# 03-Main.net
KiCad netlist of a schematic drawn in Altium Designer
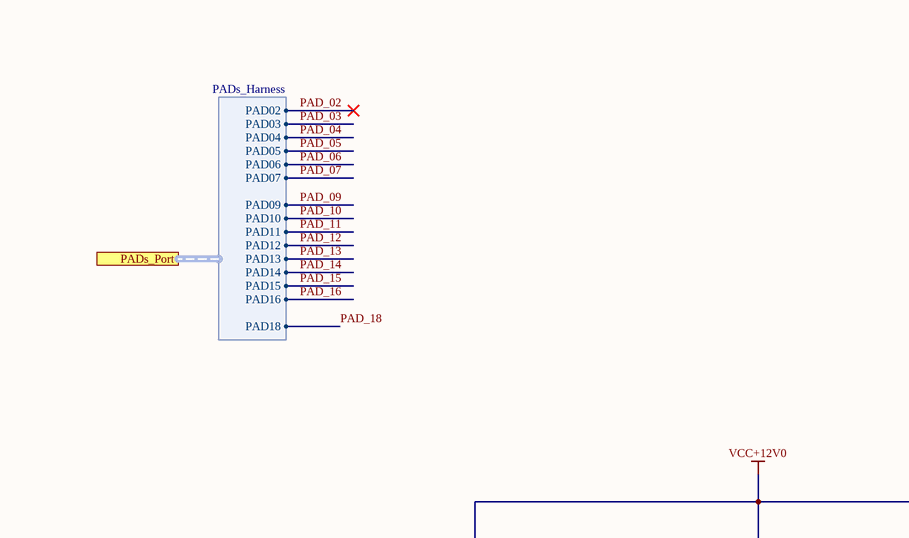
[diagram p0: 03-Main.SchDoc, top left]
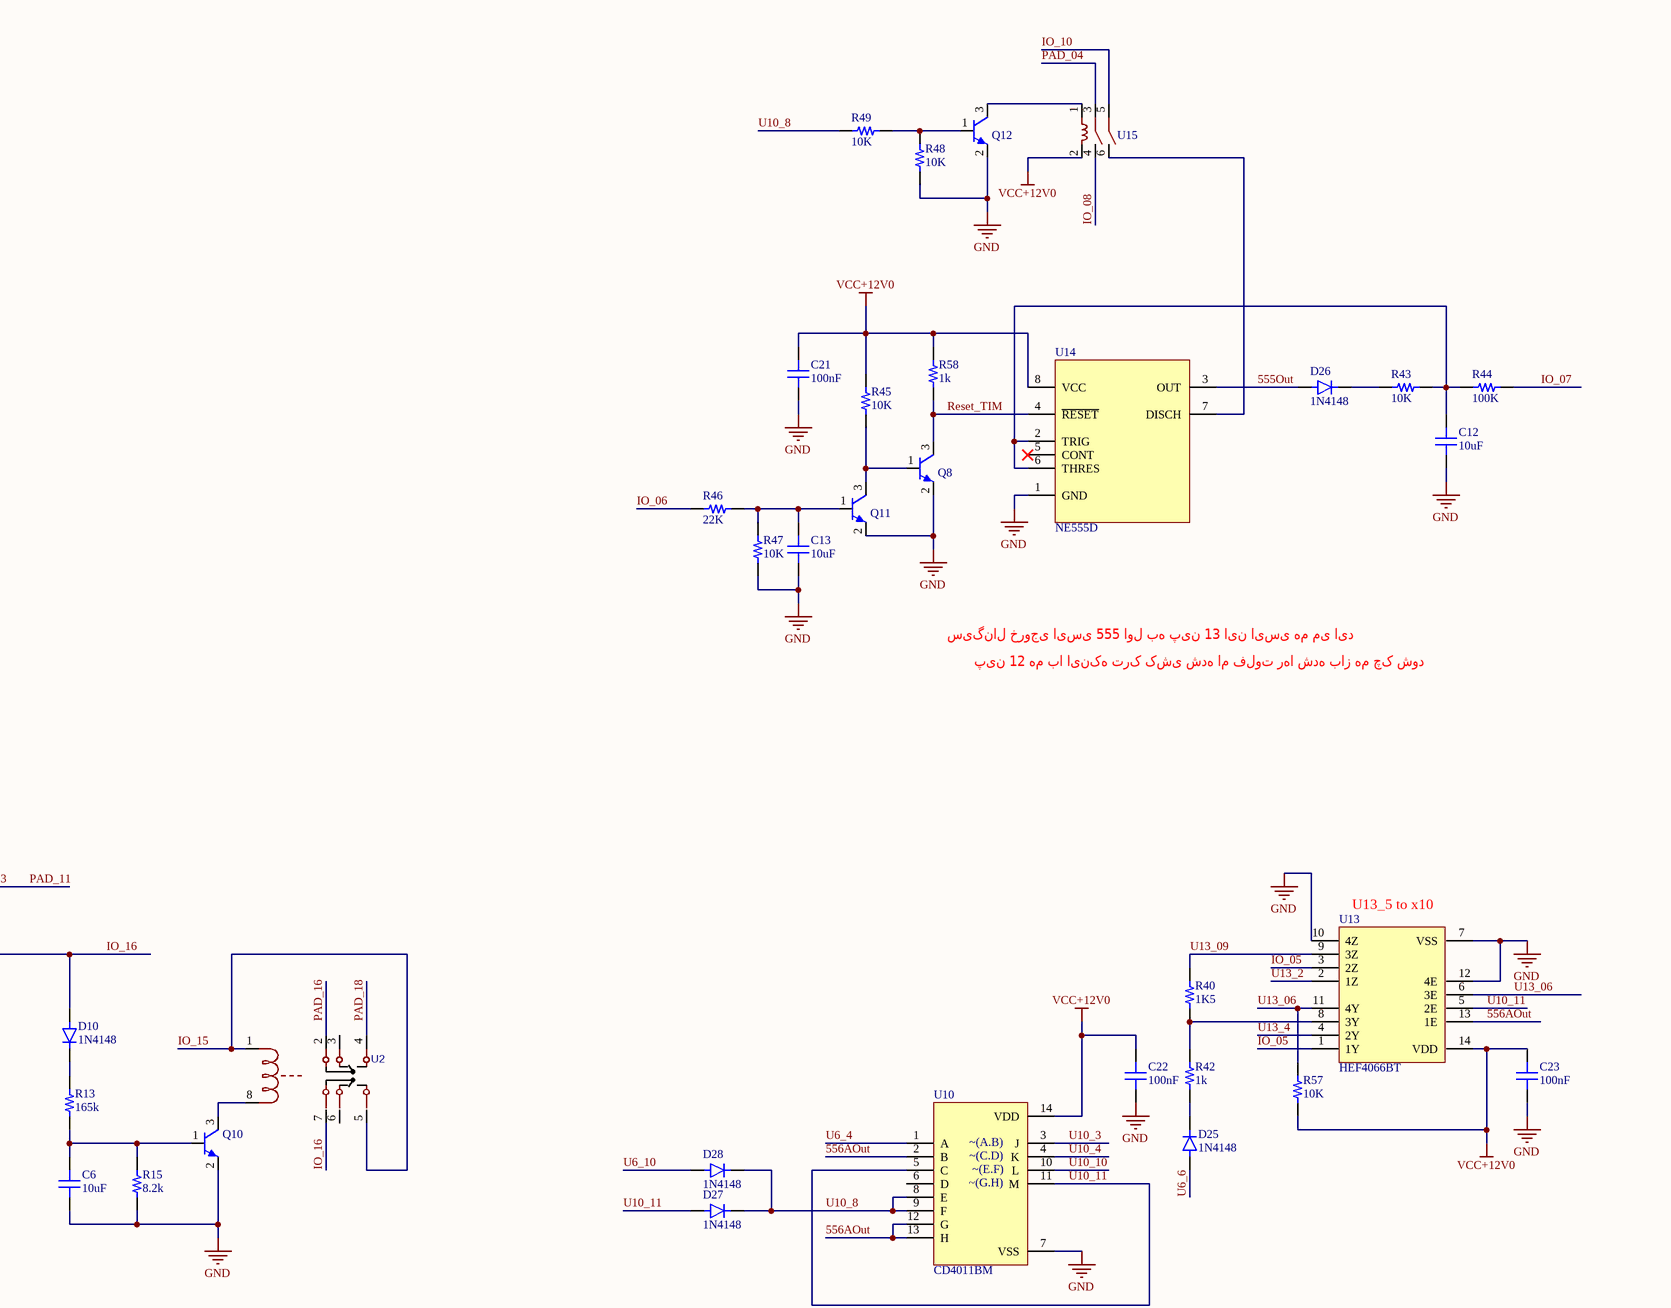
[diagram p1: 03-Main.SchDoc, top right]
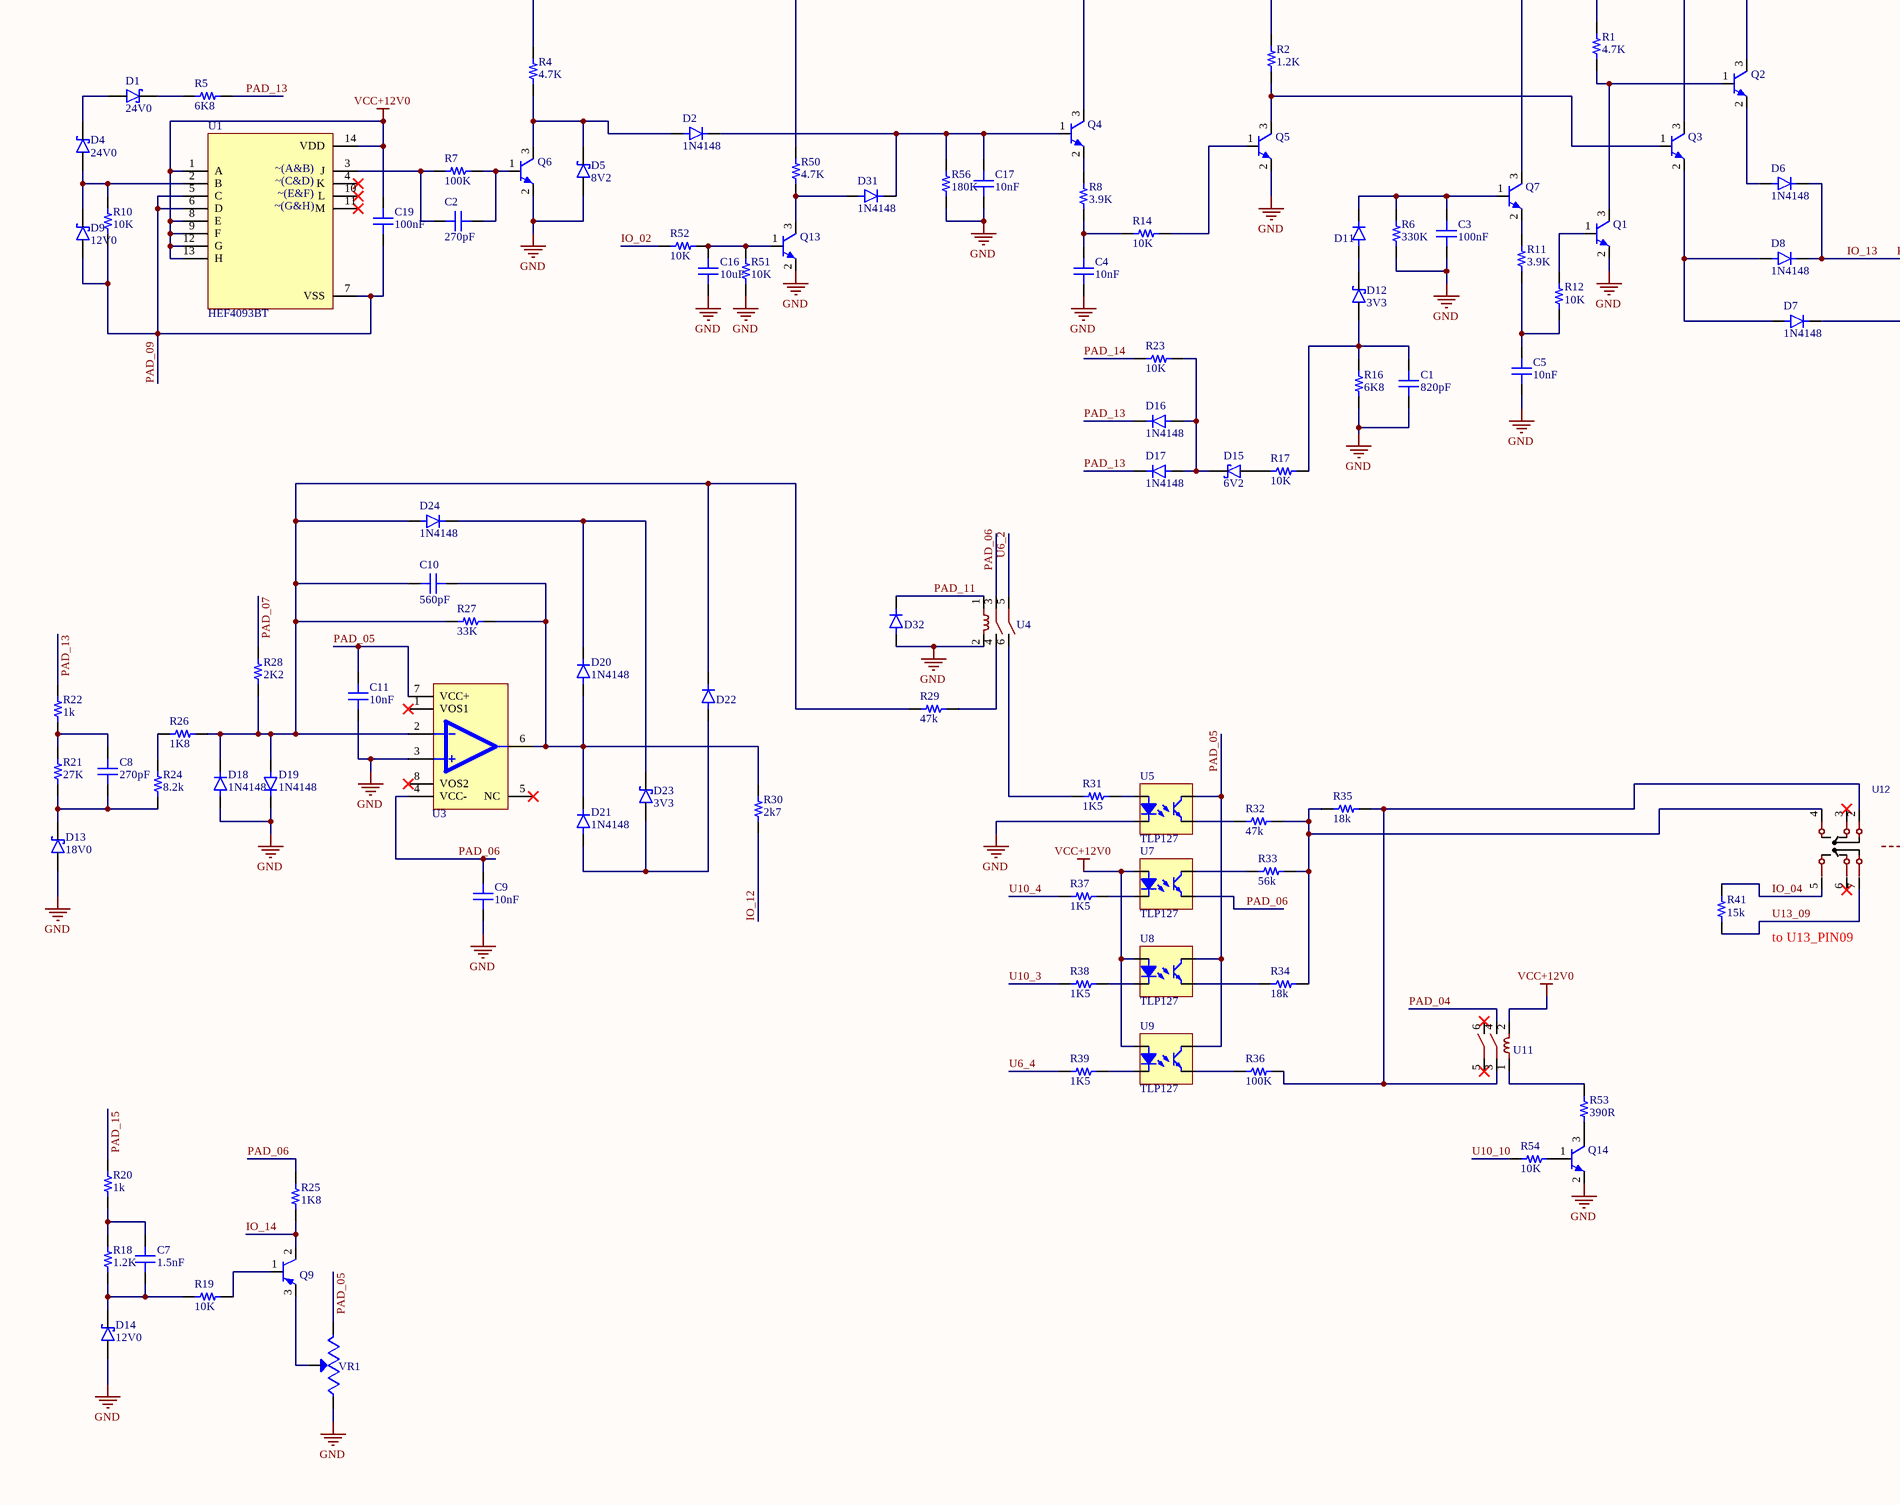
[diagram p2: 03-Main.SchDoc, bottom left]
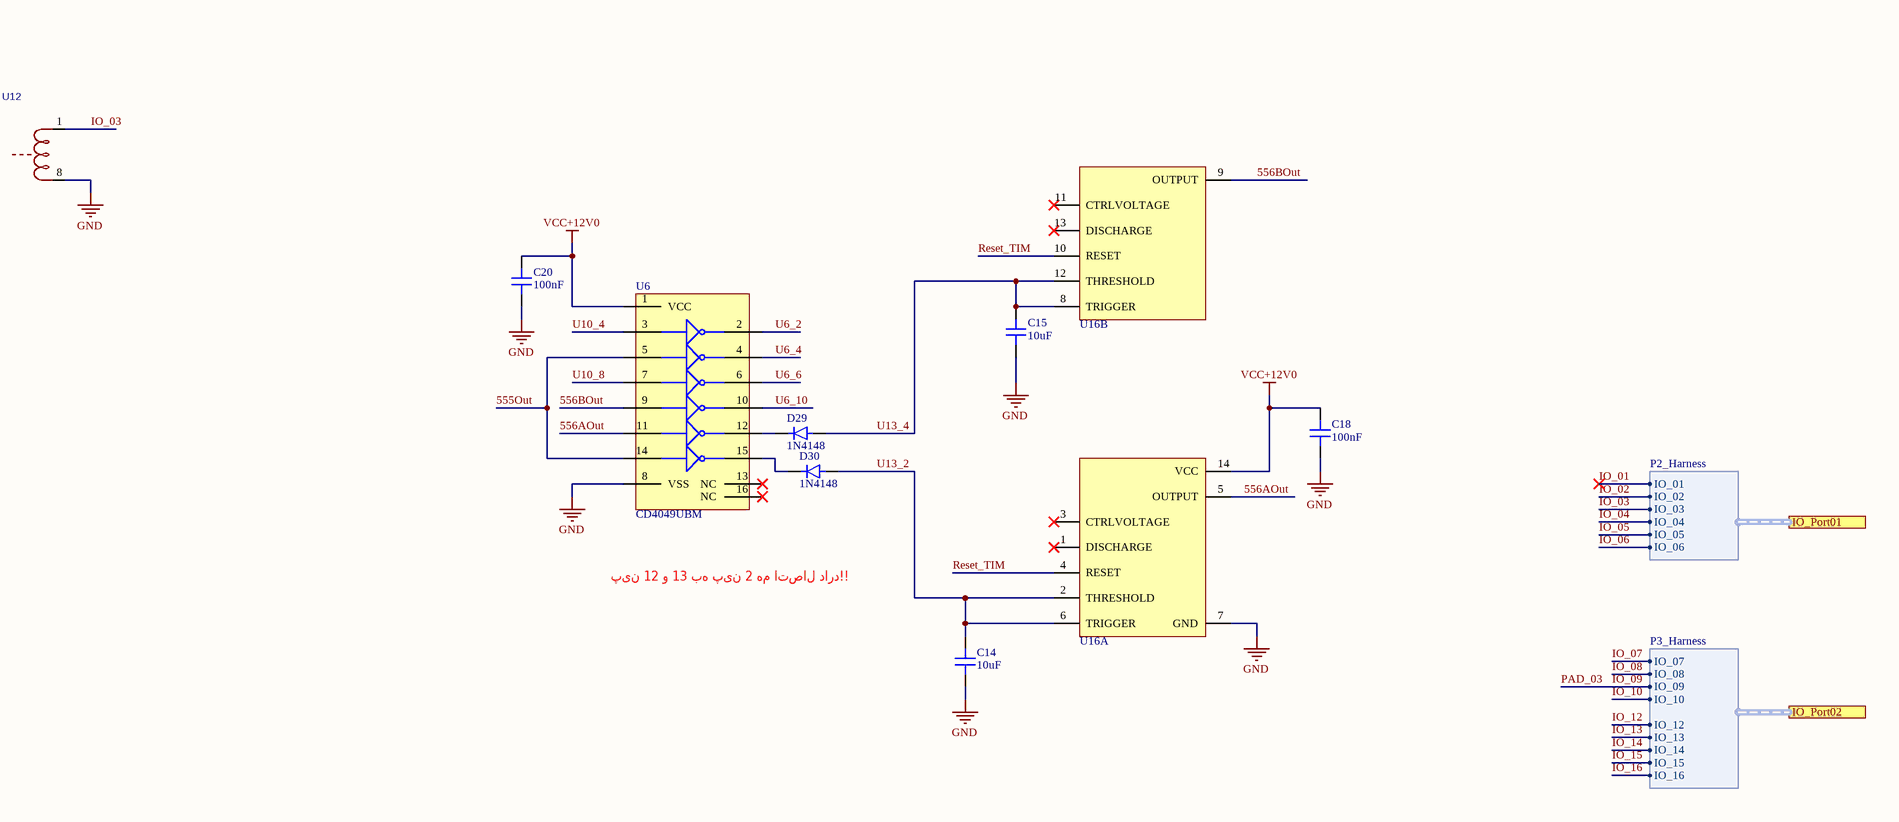
[diagram p3: 03-Main.SchDoc, bottom right]

(export (version "E")
  (design (tool "Eeschema 10.0.6"))
  (components
    (comp (ref "C1")
      (value "820pF")
      (footprint "Cap0805")
      (description "Cap 0805 820pF")
      (fields (field (name "PART NUMBER") "Cap-0805-820pF"))
      (libsource (lib "My Library") (part "Unpolarised Capacitor"))
    )
    (comp (ref "C2")
      (value "270pF")
      (footprint "Cap0805")
      (description "Cap 0805 270pF")
      (fields (field (name "PART NUMBER") "Cap-0805-270pF"))
      (libsource (lib "My Library") (part "Unpolarised Capacitor"))
    )
    (comp (ref "C3")
      (value "100nF")
      (footprint "Cap0805")
      (description "Cap 0805 100nF")
      (fields (field (name "PART NUMBER") "Cap-0805-100nF") (field (name "MANUFACTURER") "---"))
      (libsource (lib "My Library") (part "Unpolarised Capacitor"))
    )
    (comp (ref "C4")
      (value "10nF")
      (footprint "Cap0805")
      (description "Cap 0805 10nF")
      (fields (field (name "PART NUMBER") "Cap-0805-10nF"))
      (libsource (lib "My Library") (part "Unpolarised Capacitor"))
    )
    (comp (ref "C5")
      (value "10nF")
      (footprint "Cap0805")
      (description "Cap 0805 10nF")
      (fields (field (name "PART NUMBER") "Cap-0805-10nF"))
      (libsource (lib "My Library") (part "Unpolarised Capacitor"))
    )
    (comp (ref "C6")
      (value "10uF")
      (footprint "Cap0603")
      (description "Cap 0603 10uF")
      (fields (field (name "PART NUMBER") "Cap-0603-10uF") (field (name "MANUFACTURER") "---"))
      (libsource (lib "My Library") (part "Unpolarised Capacitor"))
    )
    (comp (ref "C7")
      (value "1.5nF")
      (footprint "Cap0805")
      (description "Cap 0805 1.5nF")
      (fields (field (name "PART NUMBER") "Cap-0805-1.5nF"))
      (libsource (lib "My Library") (part "Unpolarised Capacitor"))
    )
    (comp (ref "C8")
      (value "270pF")
      (footprint "Cap0805")
      (description "Cap 0805 270pF")
      (fields (field (name "PART NUMBER") "Cap-0805-270pF"))
      (libsource (lib "My Library") (part "Unpolarised Capacitor"))
    )
    (comp (ref "C9")
      (value "10nF")
      (footprint "Cap0805")
      (description "Cap 0805 10nF")
      (fields (field (name "PART NUMBER") "Cap-0805-10nF"))
      (libsource (lib "My Library") (part "Unpolarised Capacitor"))
    )
    (comp (ref "C10")
      (value "560pF")
      (footprint "Cap0603")
      (description "Cap 0603 560pF")
      (fields (field (name "PART NUMBER") "Cap-0603-560pF"))
      (libsource (lib "My Library") (part "Unpolarised Capacitor"))
    )
    (comp (ref "C11")
      (value "10nF")
      (footprint "Cap0805")
      (description "Cap 0805 10nF")
      (fields (field (name "PART NUMBER") "Cap-0805-10nF"))
      (libsource (lib "My Library") (part "Unpolarised Capacitor"))
    )
    (comp (ref "C12")
      (value "10uF")
      (footprint "Cap1206")
      (description "Cap 1206 10uF 50V")
      (fields (field (name "PART NUMBER") "Cap-1206-10uF") (field (name "MANUFACTURER") "---"))
      (libsource (lib "My Library") (part "Unpolarised Capacitor"))
    )
    (comp (ref "C13")
      (value "10uF")
      (footprint "Cap0805")
      (description "Cap 0805 10uF")
      (fields (field (name "PART NUMBER") "Cap-0805-10uF") (field (name "MANUFACTURER") "---"))
      (libsource (lib "My Library") (part "Unpolarised Capacitor"))
    )
    (comp (ref "C14")
      (value "10uF")
      (footprint "Cap1206")
      (description "Cap 1206 10uF 50V")
      (fields (field (name "PART NUMBER") "Cap-1206-10uF") (field (name "MANUFACTURER") "---"))
      (libsource (lib "My Library") (part "Unpolarised Capacitor"))
    )
    (comp (ref "C15")
      (value "10uF")
      (footprint "Cap1206")
      (description "Cap 1206 10uF 50V")
      (fields (field (name "PART NUMBER") "Cap-1206-10uF") (field (name "MANUFACTURER") "---"))
      (libsource (lib "My Library") (part "Unpolarised Capacitor"))
    )
    (comp (ref "C16")
      (value "10uF")
      (footprint "Cap1206")
      (description "Cap 1206 10uF 50V")
      (fields (field (name "PART NUMBER") "Cap-1206-10uF") (field (name "MANUFACTURER") "---"))
      (libsource (lib "My Library") (part "Unpolarised Capacitor"))
    )
    (comp (ref "C17")
      (value "10nF")
      (footprint "Cap0805")
      (description "Cap 0805 10nF")
      (fields (field (name "PART NUMBER") "Cap-0805-10nF"))
      (libsource (lib "My Library") (part "Unpolarised Capacitor"))
    )
    (comp (ref "C18")
      (value "100nF")
      (footprint "Cap0805")
      (description "Cap 0805 100nF")
      (fields (field (name "PART NUMBER") "Cap-0805-100nF") (field (name "MANUFACTURER") "---"))
      (libsource (lib "My Library") (part "Unpolarised Capacitor"))
    )
    (comp (ref "C19")
      (value "100nF")
      (footprint "Cap0805")
      (description "Cap 0805 100nF")
      (fields (field (name "PART NUMBER") "Cap-0805-100nF") (field (name "MANUFACTURER") "---"))
      (libsource (lib "My Library") (part "Unpolarised Capacitor"))
    )
    (comp (ref "C20")
      (value "100nF")
      (footprint "Cap0805")
      (description "Cap 0805 100nF")
      (fields (field (name "PART NUMBER") "Cap-0805-100nF") (field (name "MANUFACTURER") "---"))
      (libsource (lib "My Library") (part "Unpolarised Capacitor"))
    )
    (comp (ref "C21")
      (value "100nF")
      (footprint "Cap0805")
      (description "Cap 0805 100nF")
      (fields (field (name "PART NUMBER") "Cap-0805-100nF") (field (name "MANUFACTURER") "---"))
      (libsource (lib "My Library") (part "Unpolarised Capacitor"))
    )
    (comp (ref "C22")
      (value "100nF")
      (footprint "Cap0805")
      (description "Cap 0805 100nF")
      (fields (field (name "PART NUMBER") "Cap-0805-100nF") (field (name "MANUFACTURER") "---"))
      (libsource (lib "My Library") (part "Unpolarised Capacitor"))
    )
    (comp (ref "C23")
      (value "100nF")
      (footprint "Cap0805")
      (description "Cap 0805 100nF")
      (fields (field (name "PART NUMBER") "Cap-0805-100nF") (field (name "MANUFACTURER") "---"))
      (libsource (lib "My Library") (part "Unpolarised Capacitor"))
    )
    (comp (ref "D1")
      (value "24V0")
      (footprint "Melf")
      (description "Zener Diode Melf")
      (fields (field (name "MP") "TMMBAT41") (field (name "MF") "STMicroelectronics"))
      (libsource (lib "My Library") (part "Zener"))
    )
    (comp (ref "D2")
      (value "1N4148")
      (footprint "SOD-123")
      (description "Diode Standard 75 V 300mA (DC) Through Hole DO-35 Mimi Melf")
      (fields (field (name "MF") "ON Semiconductor"))
      (libsource (lib "My Library") (part "Diode"))
    )
    (comp (ref "D4")
      (value "24V0")
      (footprint "Melf")
      (description "Zener Diode Melf")
      (fields (field (name "MF") "STMicroelectronics") (field (name "MP") "TMMBAT41"))
      (libsource (lib "My Library") (part "Zener"))
    )
    (comp (ref "D5")
      (value "8V2")
      (footprint "Melf")
      (description "Zener Diode Melf")
      (fields (field (name "MP") "TMMBAT41") (field (name "MF") "STMicroelectronics"))
      (libsource (lib "My Library") (part "Zener"))
    )
    (comp (ref "D6")
      (value "1N4148")
      (footprint "SOD-123")
      (description "Diode Standard 75 V 300mA (DC) Through Hole DO-35 Mimi Melf")
      (fields (field (name "MF") "ON Semiconductor"))
      (libsource (lib "My Library") (part "Diode"))
    )
    (comp (ref "D7")
      (value "1N4148")
      (footprint "SOD-123")
      (description "Diode Standard 75 V 300mA (DC) Through Hole DO-35 Mimi Melf")
      (fields (field (name "MF") "ON Semiconductor"))
      (libsource (lib "My Library") (part "Diode"))
    )
    (comp (ref "D8")
      (value "1N4148")
      (footprint "SOD-123")
      (description "Diode Standard 75 V 300mA (DC) Through Hole DO-35 Mimi Melf")
      (fields (field (name "MF") "ON Semiconductor"))
      (libsource (lib "My Library") (part "Diode"))
    )
    (comp (ref "D9")
      (value "12V0")
      (footprint "Melf")
      (description "Zener Diode Melf")
      (fields (field (name "MP") "TMMBAT41") (field (name "MF") "STMicroelectronics"))
      (libsource (lib "My Library") (part "Zener"))
    )
    (comp (ref "D10")
      (value "1N4148")
      (footprint "SOD-123")
      (description "Diode Standard 75 V 300mA (DC) Through Hole DO-35 Mimi Melf")
      (fields (field (name "MF") "ON Semiconductor"))
      (libsource (lib "My Library") (part "Diode"))
    )
    (comp (ref "D11")
      (value "1N4148")
      (footprint "SOD-123")
      (description "Diode Standard 75 V 300mA (DC) Through Hole DO-35 Mimi Melf")
      (fields (field (name "MF") "ON Semiconductor"))
      (libsource (lib "My Library") (part "Diode"))
    )
    (comp (ref "D12")
      (value "3V3")
      (footprint "Melf")
      (description "Zener Diode Melf")
      (fields (field (name "MF") "STMicroelectronics") (field (name "MP") "TMMBAT41"))
      (libsource (lib "My Library") (part "Zener"))
    )
    (comp (ref "D13")
      (value "18V0")
      (footprint "Melf")
      (description "Zener Diode Melf")
      (fields (field (name "MF") "STMicroelectronics") (field (name "MP") "TMMBAT41"))
      (libsource (lib "My Library") (part "Zener"))
    )
    (comp (ref "D14")
      (value "12V0")
      (footprint "Melf")
      (description "Zener Diode Melf")
      (fields (field (name "MF") "STMicroelectronics") (field (name "MP") "TMMBAT41"))
      (libsource (lib "My Library") (part "Zener"))
    )
    (comp (ref "D15")
      (value "6V2")
      (footprint "Melf")
      (description "Zener Diode Melf")
      (fields (field (name "MP") "TMMBAT41") (field (name "MF") "STMicroelectronics"))
      (libsource (lib "My Library") (part "Zener"))
    )
    (comp (ref "D16")
      (value "1N4148")
      (footprint "SOD-123")
      (description "Diode Standard 75 V 300mA (DC) Through Hole DO-35 Mimi Melf")
      (fields (field (name "MF") "ON Semiconductor"))
      (libsource (lib "My Library") (part "Diode"))
    )
    (comp (ref "D17")
      (value "1N4148")
      (footprint "SOD-123")
      (description "Diode Standard 75 V 300mA (DC) Through Hole DO-35 Mimi Melf")
      (fields (field (name "MF") "ON Semiconductor"))
      (libsource (lib "My Library") (part "Diode"))
    )
    (comp (ref "D18")
      (value "1N4148")
      (footprint "SOD-123")
      (description "Diode Standard 75 V 300mA (DC) Through Hole DO-35 Mimi Melf")
      (fields (field (name "MF") "ON Semiconductor"))
      (libsource (lib "My Library") (part "Diode"))
    )
    (comp (ref "D19")
      (value "1N4148")
      (footprint "SOD-123")
      (description "Diode Standard 75 V 300mA (DC) Through Hole DO-35 Mimi Melf")
      (fields (field (name "MF") "ON Semiconductor"))
      (libsource (lib "My Library") (part "Diode"))
    )
    (comp (ref "D20")
      (value "1N4148")
      (footprint "SOD-123")
      (description "Diode Standard 75 V 300mA (DC) Through Hole DO-35 Mimi Melf")
      (fields (field (name "MF") "ON Semiconductor"))
      (libsource (lib "My Library") (part "Diode"))
    )
    (comp (ref "D21")
      (value "1N4148")
      (footprint "SOD-123")
      (description "Diode Standard 75 V 300mA (DC) Through Hole DO-35 Mimi Melf")
      (fields (field (name "MF") "ON Semiconductor"))
      (libsource (lib "My Library") (part "Diode"))
    )
    (comp (ref "D22")
      (value "1N4148")
      (footprint "SOD-123")
      (description "Diode Standard 75 V 300mA (DC) Through Hole DO-35 Mimi Melf")
      (fields (field (name "MF") "ON Semiconductor"))
      (libsource (lib "My Library") (part "Diode"))
    )
    (comp (ref "D23")
      (value "3V3")
      (footprint "MINIMELF")
      (description "Zener Diode MiniMelf")
      (fields (field (name "MF") "STMicroelectronics") (field (name "MP") "TMMBAT41"))
      (libsource (lib "My Library") (part "Zener"))
    )
    (comp (ref "D24")
      (value "1N4148")
      (footprint "SOD-123")
      (description "Diode Standard 75 V 300mA (DC) Through Hole DO-35 Mimi Melf")
      (fields (field (name "MF") "ON Semiconductor"))
      (libsource (lib "My Library") (part "Diode"))
    )
    (comp (ref "D25")
      (value "1N4148")
      (footprint "SOD-123")
      (description "Diode Standard 75 V 300mA (DC) Through Hole DO-35 Mimi Melf")
      (fields (field (name "MF") "ON Semiconductor"))
      (libsource (lib "My Library") (part "Diode"))
    )
    (comp (ref "D26")
      (value "1N4148")
      (footprint "SOD-123")
      (description "Diode Standard 75 V 300mA (DC) Through Hole DO-35 Mimi Melf")
      (fields (field (name "MF") "ON Semiconductor"))
      (libsource (lib "My Library") (part "Diode"))
    )
    (comp (ref "D27")
      (value "1N4148")
      (footprint "SOD-123")
      (description "Diode Standard 75 V 300mA (DC) Through Hole DO-35 Mimi Melf")
      (fields (field (name "MF") "ON Semiconductor"))
      (libsource (lib "My Library") (part "Diode"))
    )
    (comp (ref "D28")
      (value "1N4148")
      (footprint "SOD-123")
      (description "Diode Standard 75 V 300mA (DC) Through Hole DO-35 Mimi Melf")
      (fields (field (name "MF") "ON Semiconductor"))
      (libsource (lib "My Library") (part "Diode"))
    )
    (comp (ref "D29")
      (value "1N4148")
      (footprint "SOD-123")
      (description "Diode Standard 75 V 300mA (DC) Through Hole DO-35 Mimi Melf")
      (fields (field (name "MF") "ON Semiconductor"))
      (libsource (lib "My Library") (part "Diode"))
    )
    (comp (ref "D30")
      (value "1N4148")
      (footprint "SOD-123")
      (description "Diode Standard 75 V 300mA (DC) Through Hole DO-35 Mimi Melf")
      (fields (field (name "MF") "ON Semiconductor"))
      (libsource (lib "My Library") (part "Diode"))
    )
    (comp (ref "D31")
      (value "1N4148")
      (footprint "SOD-123")
      (description "Diode Standard 75 V 300mA (DC) Through Hole DO-35 Mimi Melf")
      (fields (field (name "MF") "ON Semiconductor"))
      (libsource (lib "My Library") (part "Diode"))
    )
    (comp (ref "D32")
      (value "1N4148")
      (footprint "SOD-123")
      (description "Diode Standard 75 V 300mA (DC) Through Hole DO-35 Mimi Melf")
      (fields (field (name "MF") "ON Semiconductor"))
      (libsource (lib "My Library") (part "Diode"))
    )
    (comp (ref "Q1")
      (value "BC337-DIP")
      (footprint "SOT54")
      (description "General Purpose Transistor 45V - 500 mA NPN")
      (fields (field (name "MANUFACTURER") "NXP"))
      (libsource (lib "My Library") (part "BJT-NPN"))
    )
    (comp (ref "Q2")
      (value "BC337-DIP")
      (footprint "SOT54")
      (description "General Purpose Transistor 45V - 500 mA NPN")
      (fields (field (name "MANUFACTURER") "NXP"))
      (libsource (lib "My Library") (part "BJT-NPN"))
    )
    (comp (ref "Q3")
      (value "BC337-DIP")
      (footprint "SOT54")
      (description "General Purpose Transistor 45V - 500 mA NPN")
      (fields (field (name "MANUFACTURER") "NXP"))
      (libsource (lib "My Library") (part "BJT-NPN"))
    )
    (comp (ref "Q4")
      (value "BC337-DIP")
      (footprint "SOT54")
      (description "General Purpose Transistor 45V - 500 mA NPN")
      (fields (field (name "MANUFACTURER") "NXP"))
      (libsource (lib "My Library") (part "BJT-NPN"))
    )
    (comp (ref "Q5")
      (value "BC337-DIP")
      (footprint "SOT54")
      (description "General Purpose Transistor 45V - 500 mA NPN")
      (fields (field (name "MANUFACTURER") "NXP"))
      (libsource (lib "My Library") (part "BJT-NPN"))
    )
    (comp (ref "Q6")
      (value "BC337-DIP")
      (footprint "SOT54")
      (description "General Purpose Transistor 45V - 500 mA NPN")
      (fields (field (name "MANUFACTURER") "NXP"))
      (libsource (lib "My Library") (part "BJT-NPN"))
    )
    (comp (ref "Q7")
      (value "BC337-DIP")
      (footprint "SOT54")
      (description "General Purpose Transistor 45V - 500 mA NPN")
      (fields (field (name "MANUFACTURER") "NXP"))
      (libsource (lib "My Library") (part "BJT-NPN"))
    )
    (comp (ref "Q8")
      (value "BC337-DIP")
      (footprint "SOT54")
      (description "General Purpose Transistor 45V - 500 mA NPN")
      (fields (field (name "MANUFACTURER") "NXP"))
      (libsource (lib "My Library") (part "BJT-NPN"))
    )
    (comp (ref "Q9")
      (value "BC177")
      (footprint "TO-18")
      (fields
        (field (name "MANUFACTURER") "---")
        (field (name "MP") "BCX53-16,115")
        (field (name "MF") "Nexperia USA")
      )
      (libsource (lib "My Library") (part "BJT-PNP"))
    )
    (comp (ref "Q10")
      (value "BC337-DIP")
      (footprint "SOT54")
      (description "General Purpose Transistor 45V - 500 mA NPN")
      (fields (field (name "MANUFACTURER") "NXP"))
      (libsource (lib "My Library") (part "BJT-NPN"))
    )
    (comp (ref "Q11")
      (value "BC337-DIP")
      (footprint "SOT54")
      (description "General Purpose Transistor 45V - 500 mA NPN")
      (fields (field (name "MANUFACTURER") "NXP"))
      (libsource (lib "My Library") (part "BJT-NPN"))
    )
    (comp (ref "Q12")
      (value "BC337-DIP")
      (footprint "SOT54")
      (description "General Purpose Transistor 45V - 500 mA NPN")
      (fields (field (name "MANUFACTURER") "NXP"))
      (libsource (lib "My Library") (part "BJT-NPN"))
    )
    (comp (ref "Q13")
      (value "BC337-DIP")
      (footprint "SOT54")
      (description "General Purpose Transistor 45V - 500 mA NPN")
      (fields (field (name "MANUFACTURER") "NXP"))
      (libsource (lib "My Library") (part "BJT-NPN"))
    )
    (comp (ref "Q14")
      (value "BC337-DIP")
      (footprint "SOT54")
      (description "General Purpose Transistor 45V - 500 mA NPN")
      (fields (field (name "MANUFACTURER") "NXP"))
      (libsource (lib "My Library") (part "BJT-NPN"))
    )
    (comp (ref "R1")
      (value "4.7K")
      (footprint "Res1206")
      (fields (field (name "PART NUMBER") "Res-1206-4.7k") (field (name "MANUFACTURER") "---"))
      (libsource (lib "My Library") (part "Resistor"))
    )
    (comp (ref "R2")
      (value "1.2K")
      (footprint "Res1206")
      (fields (field (name "PART NUMBER") "Res-1206-1.2k") (field (name "MANUFACTURER") "---"))
      (libsource (lib "My Library") (part "Resistor"))
    )
    (comp (ref "R4")
      (value "4.7K")
      (footprint "Res1206")
      (fields (field (name "PART NUMBER") "Res-1206-4.7k") (field (name "MANUFACTURER") "---"))
      (libsource (lib "My Library") (part "Resistor"))
    )
    (comp (ref "R5")
      (value "6K8")
      (footprint "Res1206")
      (description "Resistor 1206 6.8 Kohm")
      (fields (field (name "PART NUMBER") "Res-1206-6K8"))
      (libsource (lib "My Library") (part "Resistor"))
    )
    (comp (ref "R6")
      (value "330K")
      (footprint "Res1206")
      (fields (field (name "PART NUMBER") "Res-1206-330K") (field (name "MANUFACTURER") "---"))
      (libsource (lib "My Library") (part "Resistor"))
    )
    (comp (ref "R7")
      (value "100K")
      (footprint "Res1206")
      (fields (field (name "PART NUMBER") "Res-1206-100K") (field (name "MANUFACTURER") "---"))
      (libsource (lib "My Library") (part "Resistor"))
    )
    (comp (ref "R8")
      (value "3.9K")
      (footprint "Res1206")
      (fields (field (name "PART NUMBER") "Res-1206-3.9k") (field (name "MANUFACTURER") "---"))
      (libsource (lib "My Library") (part "Resistor"))
    )
    (comp (ref "R10")
      (value "10K")
      (footprint "Res1206")
      (description "Resistor 1206 10 Kohm")
      (fields (field (name "PART NUMBER") "Res-1206-10K") (field (name "MANUFACTURER") "---"))
      (libsource (lib "My Library") (part "Resistor"))
    )
    (comp (ref "R11")
      (value "3.9K")
      (footprint "Res1206")
      (fields (field (name "PART NUMBER") "Res-1206-3.9k") (field (name "MANUFACTURER") "---"))
      (libsource (lib "My Library") (part "Resistor"))
    )
    (comp (ref "R12")
      (value "10K")
      (footprint "Res1206")
      (description "Resistor 1206 10 Kohm")
      (fields (field (name "PART NUMBER") "Res-1206-10K") (field (name "MANUFACTURER") "---"))
      (libsource (lib "My Library") (part "Resistor"))
    )
    (comp (ref "R13")
      (value "165k")
      (footprint "Res1206")
      (fields (field (name "PART NUMBER") "Res-1206-165K") (field (name "MANUFACTURER") "---"))
      (libsource (lib "My Library") (part "Resistor"))
    )
    (comp (ref "R14")
      (value "10K")
      (footprint "Res1206")
      (description "Resistor 1206 10 Kohm")
      (fields (field (name "PART NUMBER") "Res-1206-10K") (field (name "MANUFACTURER") "---"))
      (libsource (lib "My Library") (part "Resistor"))
    )
    (comp (ref "R15")
      (value "8.2k")
      (footprint "Res1206")
      (fields (field (name "PART NUMBER") "Res-1206-8.2K") (field (name "MANUFACTURER") "---"))
      (libsource (lib "My Library") (part "Resistor"))
    )
    (comp (ref "R16")
      (value "6K8")
      (footprint "Res1206")
      (description "Resistor 1206 6.8 Kohm")
      (fields (field (name "PART NUMBER") "Res-1206-6K8"))
      (libsource (lib "My Library") (part "Resistor"))
    )
    (comp (ref "R17")
      (value "10K")
      (footprint "Res1206")
      (description "Resistor 1206 10 Kohm")
      (fields (field (name "PART NUMBER") "Res-1206-10K") (field (name "MANUFACTURER") "---"))
      (libsource (lib "My Library") (part "Resistor"))
    )
    (comp (ref "R18")
      (value "1.2K")
      (footprint "Res1206")
      (fields (field (name "PART NUMBER") "Res-1206-1.2k") (field (name "MANUFACTURER") "---"))
      (libsource (lib "My Library") (part "Resistor"))
    )
    (comp (ref "R19")
      (value "10K")
      (footprint "Res1206")
      (description "Resistor 1206 10 Kohm")
      (fields (field (name "PART NUMBER") "Res-1206-10K") (field (name "MANUFACTURER") "---"))
      (libsource (lib "My Library") (part "Resistor"))
    )
    (comp (ref "R20")
      (value "1k")
      (footprint "Res1206")
      (fields (field (name "PART NUMBER") "Res-1206-1K") (field (name "MANUFACTURER") "---"))
      (libsource (lib "My Library") (part "Resistor"))
    )
    (comp (ref "R21")
      (value "27K")
      (footprint "Res1206")
      (description "Resistor 1206 27 Kohm")
      (fields (field (name "PART NUMBER") "Res-1206-27K"))
      (libsource (lib "My Library") (part "Resistor"))
    )
    (comp (ref "R22")
      (value "1k")
      (footprint "Res1206")
      (fields (field (name "PART NUMBER") "Res-1206-1K") (field (name "MANUFACTURER") "---"))
      (libsource (lib "My Library") (part "Resistor"))
    )
    (comp (ref "R23")
      (value "10K")
      (footprint "Res1206")
      (description "Resistor 1206 10 Kohm")
      (fields (field (name "PART NUMBER") "Res-1206-10K") (field (name "MANUFACTURER") "---"))
      (libsource (lib "My Library") (part "Resistor"))
    )
    (comp (ref "R24")
      (value "8.2k")
      (footprint "Res1206")
      (fields (field (name "PART NUMBER") "Res-1206-8.2K") (field (name "MANUFACTURER") "---"))
      (libsource (lib "My Library") (part "Resistor"))
    )
    (comp (ref "R25")
      (value "1K8")
      (footprint "Res1206")
      (description "Resistor 1206 1.8 Kohm")
      (fields (field (name "PART NUMBER") "Res-1206-1K8"))
      (libsource (lib "My Library") (part "Resistor"))
    )
    (comp (ref "R26")
      (value "1K8")
      (footprint "Res1206")
      (description "Resistor 1206 1.8 Kohm")
      (fields (field (name "PART NUMBER") "Res-1206-1K8"))
      (libsource (lib "My Library") (part "Resistor"))
    )
    (comp (ref "R27")
      (value "33K")
      (footprint "Res1206")
      (description "Resistor 1206 33 Kohm")
      (fields (field (name "PART NUMBER") "Res-1206-33K"))
      (libsource (lib "My Library") (part "Resistor"))
    )
    (comp (ref "R28")
      (value "2K2")
      (footprint "Res1206")
      (description "Resistor 1206 2.2 Kohm")
      (fields (field (name "PART NUMBER") "Res-1206-2K2"))
      (libsource (lib "My Library") (part "Resistor"))
    )
    (comp (ref "R29")
      (value "47k")
      (footprint "Res1206")
      (fields (field (name "PART NUMBER") "Res-1206-47K") (field (name "MANUFACTURER") "---"))
      (libsource (lib "My Library") (part "Resistor"))
    )
    (comp (ref "R30")
      (value "2k7")
      (footprint "Res1206")
      (fields (field (name "PART NUMBER") "Res-1206-2K7") (field (name "MANUFACTURER") "---"))
      (libsource (lib "My Library") (part "Resistor"))
    )
    (comp (ref "R31")
      (value "1K5")
      (footprint "Res1206")
      (description "Resistor 1206 1.5 Kohm")
      (fields (field (name "PART NUMBER") "Res-1206-1K5"))
      (libsource (lib "My Library") (part "Resistor"))
    )
    (comp (ref "R32")
      (value "47k")
      (footprint "Res1206")
      (fields (field (name "PART NUMBER") "Res-1206-47K") (field (name "MANUFACTURER") "---"))
      (libsource (lib "My Library") (part "Resistor"))
    )
    (comp (ref "R33")
      (value "56k")
      (footprint "Res1206")
      (fields (field (name "PART NUMBER") "Res-1206-56K") (field (name "MANUFACTURER") "---"))
      (libsource (lib "My Library") (part "Resistor"))
    )
    (comp (ref "R34")
      (value "18k")
      (footprint "Res1206")
      (fields (field (name "PART NUMBER") "Res-1206-18K") (field (name "MANUFACTURER") "---"))
      (libsource (lib "My Library") (part "Resistor"))
    )
    (comp (ref "R35")
      (value "18k")
      (footprint "Res1206")
      (fields (field (name "PART NUMBER") "Res-1206-18K") (field (name "MANUFACTURER") "---"))
      (libsource (lib "My Library") (part "Resistor"))
    )
    (comp (ref "R36")
      (value "100K")
      (footprint "Res1206")
      (fields (field (name "PART NUMBER") "Res-1206-100K") (field (name "MANUFACTURER") "---"))
      (libsource (lib "My Library") (part "Resistor"))
    )
    (comp (ref "R37")
      (value "1K5")
      (footprint "Res1206")
      (description "Resistor 1206 1.5 Kohm")
      (fields (field (name "PART NUMBER") "Res-1206-1K5"))
      (libsource (lib "My Library") (part "Resistor"))
    )
    (comp (ref "R38")
      (value "1K5")
      (footprint "Res1206")
      (description "Resistor 1206 1.5 Kohm")
      (fields (field (name "PART NUMBER") "Res-1206-1K5"))
      (libsource (lib "My Library") (part "Resistor"))
    )
    (comp (ref "R39")
      (value "1K5")
      (footprint "Res1206")
      (description "Resistor 1206 1.5 Kohm")
      (fields (field (name "PART NUMBER") "Res-1206-1K5"))
      (libsource (lib "My Library") (part "Resistor"))
    )
    (comp (ref "R40")
      (value "1K5")
      (footprint "Res1206")
      (description "Resistor 1206 1.5 Kohm")
      (fields (field (name "PART NUMBER") "Res-1206-1K5"))
      (libsource (lib "My Library") (part "Resistor"))
    )
    (comp (ref "R41")
      (value "15k")
      (footprint "Res1206")
      (fields (field (name "PART NUMBER") "Res-1206-15k") (field (name "MANUFACTURER") "---"))
      (libsource (lib "My Library") (part "Resistor"))
    )
    (comp (ref "R42")
      (value "1k")
      (footprint "Res1206")
      (fields (field (name "PART NUMBER") "Res-1206-1K") (field (name "MANUFACTURER") "---"))
      (libsource (lib "My Library") (part "Resistor"))
    )
    (comp (ref "R43")
      (value "10K")
      (footprint "Res1206")
      (description "Resistor 1206 10 Kohm")
      (fields (field (name "PART NUMBER") "Res-1206-10K") (field (name "MANUFACTURER") "---"))
      (libsource (lib "My Library") (part "Resistor"))
    )
    (comp (ref "R44")
      (value "100K")
      (footprint "Res1206")
      (fields (field (name "PART NUMBER") "Res-1206-100K") (field (name "MANUFACTURER") "---"))
      (libsource (lib "My Library") (part "Resistor"))
    )
    (comp (ref "R45")
      (value "10K")
      (footprint "Res1206")
      (description "Resistor 1206 10 Kohm")
      (fields (field (name "PART NUMBER") "Res-1206-10K") (field (name "MANUFACTURER") "---"))
      (libsource (lib "My Library") (part "Resistor"))
    )
    (comp (ref "R46")
      (value "22K")
      (footprint "Res1206")
      (description "Resistor 1206 22 Kohm")
      (fields (field (name "PART NUMBER") "Res-1206-22K"))
      (libsource (lib "My Library") (part "Resistor"))
    )
    (comp (ref "R47")
      (value "10K")
      (footprint "Res1206")
      (description "Resistor 1206 10 Kohm")
      (fields (field (name "PART NUMBER") "Res-1206-10K") (field (name "MANUFACTURER") "---"))
      (libsource (lib "My Library") (part "Resistor"))
    )
    (comp (ref "R48")
      (value "10K")
      (footprint "Res1206")
      (description "Resistor 1206 10 Kohm")
      (fields (field (name "PART NUMBER") "Res-1206-10K") (field (name "MANUFACTURER") "---"))
      (libsource (lib "My Library") (part "Resistor"))
    )
    (comp (ref "R49")
      (value "10K")
      (footprint "Res1206")
      (description "Resistor 1206 10 Kohm")
      (fields (field (name "PART NUMBER") "Res-1206-10K") (field (name "MANUFACTURER") "---"))
      (libsource (lib "My Library") (part "Resistor"))
    )
    (comp (ref "R50")
      (value "4.7K")
      (footprint "Res1206")
      (fields (field (name "PART NUMBER") "Res-1206-4.7k") (field (name "MANUFACTURER") "---"))
      (libsource (lib "My Library") (part "Resistor"))
    )
    (comp (ref "R51")
      (value "10K")
      (footprint "Res1206")
      (description "Resistor 1206 10 Kohm")
      (fields (field (name "PART NUMBER") "Res-1206-10K") (field (name "MANUFACTURER") "---"))
      (libsource (lib "My Library") (part "Resistor"))
    )
    (comp (ref "R52")
      (value "10K")
      (footprint "Res1206")
      (description "Resistor 1206 10 Kohm")
      (fields (field (name "PART NUMBER") "Res-1206-10K") (field (name "MANUFACTURER") "---"))
      (libsource (lib "My Library") (part "Resistor"))
    )
    (comp (ref "R53")
      (value "390R")
      (footprint "Res1206")
      (fields (field (name "PART NUMBER") "Res-1206-390R") (field (name "MANUFACTURER") "---"))
      (libsource (lib "My Library") (part "Resistor"))
    )
    (comp (ref "R54")
      (value "10K")
      (footprint "Res1206")
      (description "Resistor 1206 10 Kohm")
      (fields (field (name "PART NUMBER") "Res-1206-10K") (field (name "MANUFACTURER") "---"))
      (libsource (lib "My Library") (part "Resistor"))
    )
    (comp (ref "R56")
      (value "180K")
      (footprint "Res1206")
      (description "Resistor 1206 180K")
      (fields (field (name "PART NUMBER") "Res-1206-180K"))
      (libsource (lib "My Library") (part "Resistor"))
    )
    (comp (ref "R57")
      (value "10K")
      (footprint "Res1206")
      (description "Resistor 1206 10 Kohm")
      (fields (field (name "PART NUMBER") "Res-1206-10K") (field (name "MANUFACTURER") "---"))
      (libsource (lib "My Library") (part "Resistor"))
    )
    (comp (ref "R58")
      (value "1k")
      (footprint "Res1206")
      (fields (field (name "PART NUMBER") "Res-1206-1K") (field (name "MANUFACTURER") "---"))
      (libsource (lib "My Library") (part "Resistor"))
    )
    (comp (ref "U1")
      (value "HEF4093BT")
      (footprint "SOIC-14")
      (description "2 input NAND schmitt trigger with 4 channel")
      (libsource (lib "My Library") (part "HCF4093BE"))
    )
    (comp (ref "U2")
      (value "HRS2H-S-DC24V")
      (footprint "HRS2H-S-DC24V")
      (description "Relay with 2 contact and 24VDC with 1A current")
      (fields (field (name "MANUFACTURER") "HUIGANG"))
      (libsource (lib "My Library") (part "HRS2H-S-DC24V"))
    )
    (comp (ref "U3")
      (value "OP07CD")
      (footprint "SOP8")
      (description "Low-Offset voltage (0.25mV) single operational amplifier 8-SOIC 0 to 70")
      (fields (field (name "MF") "Texas Instruments") (field (name "MANUFACTURER") "Analog Device"))
      (libsource (lib "My Library") (part "OP07CD"))
    )
    (comp (ref "U4")
      (value "OL-C-212H")
      (footprint "ol-c-212H")
      (description "REED RELAY  2 Contact")
      (libsource (lib "My Library") (part "ol-c-212H"))
    )
    (comp (ref "U5")
      (value "TLP127")
      (footprint "TLP127")
      (description "typical Optocoupler with 1 channel and DIP")
      (fields (field (name "PART NUMBER") "TLP127smd"))
      (libsource (lib "My Library") (part "TLP521-1"))
    )
    (comp (ref "U6")
      (value "CD4049UBM")
      (footprint "SOIC-16")
      (description "6-ch, 3-V to 18-V inverters")
      (fields (field (name "MANUFACTURER") "Texas Instrument"))
      (libsource (lib "My Library") (part "CD4049UBE"))
    )
    (comp (ref "U7")
      (value "TLP127")
      (footprint "TLP127")
      (description "typical Optocoupler with 1 channel and DIP")
      (fields (field (name "PART NUMBER") "TLP127smd"))
      (libsource (lib "My Library") (part "TLP521-1"))
    )
    (comp (ref "U8")
      (value "TLP127")
      (footprint "TLP127")
      (description "typical Optocoupler with 1 channel and DIP")
      (fields (field (name "PART NUMBER") "TLP127smd"))
      (libsource (lib "My Library") (part "TLP521-1"))
    )
    (comp (ref "U9")
      (value "TLP127")
      (footprint "TLP127")
      (description "typical Optocoupler with 1 channel and DIP")
      (fields (field (name "PART NUMBER") "TLP127smd"))
      (libsource (lib "My Library") (part "TLP521-1"))
    )
    (comp (ref "U10")
      (value "CD4011BM")
      (footprint "SOIC-14")
      (fields (field (name "MP") "CD4011BE") (field (name "MANUFACTURER") "Texas Instrument"))
      (libsource (lib "My Library") (part "CD4011BE"))
    )
    (comp (ref "U11")
      (value "OL-C-212H")
      (footprint "ol-c-212H")
      (description "REED RELAY  2 Contact")
      (libsource (lib "My Library") (part "ol-c-212H"))
    )
    (comp (ref "U12")
      (value "HRS2H-S-DC24V")
      (footprint "HRS2H-S-DC24V")
      (description "Relay with 2 contact and 24VDC with 1A current")
      (fields (field (name "MANUFACTURER") "HUIGANG"))
      (libsource (lib "") (part "HRS2H-S-DC24V_1"))
    )
    (comp (ref "U13")
      (value "HEF4066BT")
      (footprint "SOIC-14")
      (description "4 Channel Circuit Analog IC Switch 1:1 with Enable")
      (fields (field (name "MF") "NXP Semiconductors") (field (name "MANUFACTURER") "Nexperia"))
      (libsource (lib "My Library") (part "HEF4066BT"))
    )
    (comp (ref "U14")
      (value "NE555D")
      (footprint "SOP8")
      (description "555 Type, Timer/Oscillator (Single) IC 500kHz 8-SOIC")
      (fields (field (name "MF") "STMicroelectronics") (field (name "MANUFACTURER") "ST"))
      (libsource (lib "My Library") (part "NE555D"))
    )
    (comp (ref "U15")
      (value "OL-C-212H")
      (footprint "ol-c-212H")
      (description "REED RELAY  2 Contact")
      (libsource (lib "My Library") (part "ol-c-212H"))
    )
    (comp (ref "U16")
      (value "NE556D")
      (footprint "SOIC-14")
      (description "Dual 555 Timer 500kHz")
      (fields (field (name "MF") "STMicroelectronics") (field (name "MANUFACTURER") "ST"))
      (libsource (lib "My Library") (part "NE556D"))
    )
    (comp (ref "VR1")
      (value "10k")
      (footprint "Multi_Turn")
      (description "Resistor Variable Multi turn")
      (fields (field (name "PART NUMBER") "Res Variable") (field (name "MP") "3296W-OT1-204"))
      (libsource (lib "My Library") (part "RVar"))
    )
  )
  (nets
    (net (code "4") (name "/555Out") (class "Default")
      (node (ref "D26") (pin "A") (pinfunction "A_A") (pintype "passive"))
      (node (ref "U14") (pin "3") (pinfunction "OUT_3") (pintype "passive"))
      (node (ref "U6") (pin "14") (pinfunction "F_14") (pintype "passive"))
      (node (ref "U6") (pin "5") (pinfunction "B_5") (pintype "passive"))
    )
    (net (code "5") (name "/556AOut") (class "Default")
      (node (ref "U10") (pin "12") (pinfunction "G_12") (pintype "passive"))
      (node (ref "U10") (pin "13") (pinfunction "H_13") (pintype "passive"))
      (node (ref "U10") (pin "2") (pinfunction "B_2") (pintype "passive"))
      (node (ref "U13") (pin "13") (pinfunction "1E_13") (pintype "passive"))
      (node (ref "U16") (pin "5") (pinfunction "OUTPUT_5") (pintype "passive"))
      (node (ref "U6") (pin "11") (pinfunction "E_11") (pintype "passive"))
    )
    (net (code "6") (name "/556BOut") (class "Default")
      (node (ref "U16") (pin "9") (pinfunction "OUTPUT_9") (pintype "passive"))
      (node (ref "U6") (pin "9") (pinfunction "D_9") (pintype "passive"))
    )
    (net (code "8") (name "/IO_02") (class "Default")
      (node (ref "R52") (pin "2") (pinfunction "2_2") (pintype "passive"))
    )
    (net (code "9") (name "/IO_03") (class "Default")
      (node (ref "U12") (pin "1") (pinfunction "1_1") (pintype "passive"))
    )
    (net (code "10") (name "/IO_04") (class "Default")
      (node (ref "R41") (pin "2") (pinfunction "2_2") (pintype "passive"))
      (node (ref "U12") (pin "5") (pinfunction "5_5") (pintype "passive"))
    )
    (net (code "11") (name "/IO_05") (class "Default")
      (node (ref "U13") (pin "1") (pinfunction "1Y_1") (pintype "passive"))
      (node (ref "U13") (pin "3") (pinfunction "2Z_3") (pintype "passive"))
    )
    (net (code "12") (name "/IO_06") (class "Default")
      (node (ref "R46") (pin "1") (pinfunction "1_1") (pintype "passive"))
    )
    (net (code "13") (name "/IO_07") (class "Default")
      (node (ref "R44") (pin "1") (pinfunction "1_1") (pintype "passive"))
    )
    (net (code "14") (name "/IO_08") (class "Default")
      (node (ref "U15") (pin "4") (pinfunction "4_4") (pintype "passive"))
    )
    (net (code "16") (name "/IO_10") (class "Default")
      (node (ref "U15") (pin "5") (pinfunction "5_5") (pintype "passive"))
    )
    (net (code "17") (name "/IO_12") (class "Default")
      (node (ref "R30") (pin "1") (pinfunction "1_1") (pintype "passive"))
    )
    (net (code "18") (name "/IO_13") (class "Default")
      (node (ref "D32") (pin "C") (pinfunction "C_C") (pintype "passive"))
      (node (ref "D6") (pin "C") (pinfunction "C_C") (pintype "passive"))
      (node (ref "D8") (pin "C") (pinfunction "C_C") (pintype "passive"))
      (node (ref "U4") (pin "1") (pinfunction "1_1") (pintype "passive"))
    )
    (net (code "19") (name "/IO_14") (class "Default")
      (node (ref "Q9") (pin "2") (pinfunction "C_2") (pintype "passive"))
      (node (ref "R25") (pin "2") (pinfunction "2_2") (pintype "passive"))
    )
    (net (code "20") (name "/IO_15") (class "Default")
      (node (ref "U2") (pin "1") (pinfunction "1_1") (pintype "passive"))
      (node (ref "U2") (pin "5") (pinfunction "5_5") (pintype "passive"))
    )
    (net (code "21") (name "/IO_16") (class "Default")
      (node (ref "D10") (pin "A") (pinfunction "A_A") (pintype "passive"))
      (node (ref "D7") (pin "C") (pinfunction "C_C") (pintype "passive"))
      (node (ref "U2") (pin "7") (pinfunction "7_7") (pintype "passive"))
    )
    (net (code "23") (name "/PAD_04") (class "Default")
      (node (ref "U11") (pin "4") (pinfunction "4_4") (pintype "passive"))
      (node (ref "U15") (pin "3") (pinfunction "3_3") (pintype "passive"))
    )
    (net (code "24") (name "/PAD_05") (class "Default")
      (node (ref "C11") (pin "2") (pinfunction "2_2") (pintype "passive"))
      (node (ref "U3") (pin "7") (pinfunction "VCC+_7") (pintype "power_in"))
      (node (ref "U5") (pin "4") (pinfunction "4_4") (pintype "passive"))
      (node (ref "U8") (pin "4") (pinfunction "4_4") (pintype "passive"))
      (node (ref "U9") (pin "4") (pinfunction "4_4") (pintype "passive"))
      (node (ref "VR1") (pin "3") (pinfunction "CW_3") (pintype "passive"))
    )
    (net (code "25") (name "/PAD_06") (class "Default")
      (node (ref "C9") (pin "2") (pinfunction "2_2") (pintype "passive"))
      (node (ref "R25") (pin "1") (pinfunction "1_1") (pintype "passive"))
      (node (ref "U3") (pin "4") (pinfunction "VCC-_4") (pintype "power_in"))
      (node (ref "U4") (pin "3") (pinfunction "3_3") (pintype "passive"))
      (node (ref "U7") (pin "3") (pinfunction "3_3") (pintype "passive"))
    )
    (net (code "26") (name "/PAD_07") (class "Default")
      (node (ref "R28") (pin "1") (pinfunction "1_1") (pintype "passive"))
    )
    (net (code "27") (name "/PAD_09") (class "Default")
      (node (ref "C19") (pin "1") (pinfunction "1_1") (pintype "passive"))
      (node (ref "D9") (pin "A") (pinfunction "A_A") (pintype "passive"))
      (node (ref "R10") (pin "1") (pinfunction "1_1") (pintype "passive"))
      (node (ref "U1") (pin "5") (pinfunction "C_5") (pintype "passive"))
      (node (ref "U1") (pin "6") (pinfunction "D_6") (pintype "passive"))
      (node (ref "U1") (pin "7") (pinfunction "VSS_7") (pintype "power_in"))
    )
    (net (code "30") (name "/PAD_13") (class "Default")
      (node (ref "D16") (pin "C") (pinfunction "C_C") (pintype "passive"))
      (node (ref "D17") (pin "C") (pinfunction "C_C") (pintype "passive"))
      (node (ref "R22") (pin "1") (pinfunction "1_1") (pintype "passive"))
      (node (ref "R5") (pin "2") (pinfunction "2_2") (pintype "passive"))
    )
    (net (code "31") (name "/PAD_14") (class "Default")
      (node (ref "R23") (pin "1") (pinfunction "1_1") (pintype "passive"))
    )
    (net (code "32") (name "/PAD_15") (class "Default")
      (node (ref "R20") (pin "1") (pinfunction "1_1") (pintype "passive"))
    )
    (net (code "33") (name "/PAD_16") (class "Default")
      (node (ref "U2") (pin "2") (pinfunction "2_2") (pintype "passive"))
    )
    (net (code "34") (name "/PAD_18") (class "Default")
      (node (ref "U2") (pin "4") (pinfunction "4_4") (pintype "passive"))
    )
    (net (code "35") (name "/Reset_TIM") (class "Default")
      (node (ref "Q8") (pin "3") (pinfunction "C_3") (pintype "passive"))
      (node (ref "R58") (pin "1") (pinfunction "1_1") (pintype "passive"))
      (node (ref "U14") (pin "4") (pinfunction "~{RESET}_4") (pintype "passive"))
      (node (ref "U16") (pin "10") (pinfunction "RESET_10") (pintype "passive"))
      (node (ref "U16") (pin "4") (pinfunction "RESET_4") (pintype "passive"))
    )
    (net (code "36") (name "/U6_2") (class "Default")
      (node (ref "U4") (pin "5") (pinfunction "5_5") (pintype "passive"))
      (node (ref "U6") (pin "2") (pinfunction "G_2") (pintype "passive"))
    )
    (net (code "37") (name "/U6_4") (class "Default")
      (node (ref "R39") (pin "1") (pinfunction "1_1") (pintype "passive"))
      (node (ref "U10") (pin "1") (pinfunction "A_1") (pintype "passive"))
      (node (ref "U6") (pin "4") (pinfunction "H_4") (pintype "passive"))
    )
    (net (code "38") (name "/U6_6") (class "Default")
      (node (ref "D25") (pin "A") (pinfunction "A_A") (pintype "passive"))
      (node (ref "U6") (pin "6") (pinfunction "I_6") (pintype "passive"))
    )
    (net (code "39") (name "/U6_10") (class "Default")
      (node (ref "D28") (pin "A") (pinfunction "A_A") (pintype "passive"))
      (node (ref "U6") (pin "10") (pinfunction "J_10") (pintype "passive"))
    )
    (net (code "40") (name "/U10_3") (class "Default")
      (node (ref "R38") (pin "1") (pinfunction "1_1") (pintype "passive"))
      (node (ref "U10") (pin "3") (pinfunction "J_3") (pintype "passive"))
    )
    (net (code "41") (name "/U10_4") (class "Default")
      (node (ref "R37") (pin "1") (pinfunction "1_1") (pintype "passive"))
      (node (ref "U10") (pin "4") (pinfunction "K_4") (pintype "passive"))
      (node (ref "U6") (pin "3") (pinfunction "A_3") (pintype "passive"))
    )
    (net (code "42") (name "/U10_8") (class "Default")
      (node (ref "D27") (pin "C") (pinfunction "C_C") (pintype "passive"))
      (node (ref "D28") (pin "C") (pinfunction "C_C") (pintype "passive"))
      (node (ref "R49") (pin "2") (pinfunction "2_2") (pintype "passive"))
      (node (ref "U10") (pin "8") (pinfunction "E_8") (pintype "passive"))
      (node (ref "U10") (pin "9") (pinfunction "F_9") (pintype "passive"))
      (node (ref "U6") (pin "7") (pinfunction "C_7") (pintype "passive"))
    )
    (net (code "43") (name "/U10_10") (class "Default")
      (node (ref "R54") (pin "2") (pinfunction "2_2") (pintype "passive"))
      (node (ref "U10") (pin "10") (pinfunction "L_10") (pintype "passive"))
    )
    (net (code "44") (name "/U10_11") (class "Default")
      (node (ref "D27") (pin "A") (pinfunction "A_A") (pintype "passive"))
      (node (ref "U10") (pin "11") (pinfunction "M_11") (pintype "passive"))
      (node (ref "U10") (pin "5") (pinfunction "C_5") (pintype "passive"))
      (node (ref "U13") (pin "5") (pinfunction "2E_5") (pintype "passive"))
    )
    (net (code "45") (name "/U13_2") (class "Default")
      (node (ref "C14") (pin "2") (pinfunction "2_2") (pintype "passive"))
      (node (ref "D30") (pin "A") (pinfunction "A_A") (pintype "passive"))
      (node (ref "U13") (pin "2") (pinfunction "1Z_2") (pintype "passive"))
      (node (ref "U16") (pin "2") (pinfunction "THRESHOLD_2") (pintype "passive"))
      (node (ref "U16") (pin "6") (pinfunction "TRIGGER_6") (pintype "passive"))
    )
    (net (code "46") (name "/U13_4") (class "Default")
      (node (ref "C15") (pin "2") (pinfunction "2_2") (pintype "passive"))
      (node (ref "D29") (pin "A") (pinfunction "A_A") (pintype "passive"))
      (node (ref "U13") (pin "4") (pinfunction "2Y_4") (pintype "passive"))
      (node (ref "U16") (pin "12") (pinfunction "THRESHOLD_12") (pintype "passive"))
      (node (ref "U16") (pin "8") (pinfunction "TRIGGER_8") (pintype "passive"))
    )
    (net (code "47") (name "/U13_06") (class "Default")
      (node (ref "R57") (pin "2") (pinfunction "2_2") (pintype "passive"))
      (node (ref "U13") (pin "11") (pinfunction "4Y_11") (pintype "passive"))
      (node (ref "U13") (pin "6") (pinfunction "3E_6") (pintype "passive"))
    )
    (net (code "48") (name "/U13_09") (class "Default")
      (node (ref "R40") (pin "1") (pinfunction "1_1") (pintype "passive"))
      (node (ref "R41") (pin "1") (pinfunction "1_1") (pintype "passive"))
      (node (ref "U12") (pin "7") (pinfunction "7_7") (pintype "passive"))
      (node (ref "U13") (pin "9") (pinfunction "3Z_9") (pintype "passive"))
    )
    (net (code "52") (name "GND") (class "Default")
      (node (ref "C1") (pin "1") (pinfunction "1_1") (pintype "passive"))
      (node (ref "C11") (pin "1") (pinfunction "1_1") (pintype "passive"))
      (node (ref "C12") (pin "1") (pinfunction "1_1") (pintype "passive"))
      (node (ref "C13") (pin "1") (pinfunction "1_1") (pintype "passive"))
      (node (ref "C14") (pin "1") (pinfunction "1_1") (pintype "passive"))
      (node (ref "C15") (pin "1") (pinfunction "1_1") (pintype "passive"))
      (node (ref "C16") (pin "2") (pinfunction "2_2") (pintype "passive"))
      (node (ref "C17") (pin "2") (pinfunction "2_2") (pintype "passive"))
      (node (ref "C18") (pin "2") (pinfunction "2_2") (pintype "passive"))
      (node (ref "C20") (pin "1") (pinfunction "1_1") (pintype "passive"))
      (node (ref "C21") (pin "2") (pinfunction "2_2") (pintype "passive"))
      (node (ref "C22") (pin "1") (pinfunction "1_1") (pintype "passive"))
      (node (ref "C23") (pin "2") (pinfunction "2_2") (pintype "passive"))
      (node (ref "C3") (pin "2") (pinfunction "2_2") (pintype "passive"))
      (node (ref "C4") (pin "1") (pinfunction "1_1") (pintype "passive"))
      (node (ref "C5") (pin "1") (pinfunction "1_1") (pintype "passive"))
      (node (ref "C6") (pin "1") (pinfunction "1_1") (pintype "passive"))
      (node (ref "C9") (pin "1") (pinfunction "1_1") (pintype "passive"))
      (node (ref "D13") (pin "A") (pinfunction "A_A") (pintype "passive"))
      (node (ref "D14") (pin "A") (pinfunction "A_A") (pintype "passive"))
      (node (ref "D18") (pin "A") (pinfunction "A_A") (pintype "passive"))
      (node (ref "D19") (pin "C") (pinfunction "C_C") (pintype "passive"))
      (node (ref "D32") (pin "A") (pinfunction "A_A") (pintype "passive"))
      (node (ref "D5") (pin "A") (pinfunction "A_A") (pintype "passive"))
      (node (ref "Q1") (pin "2") (pinfunction "E_2") (pintype "passive"))
      (node (ref "Q10") (pin "2") (pinfunction "E_2") (pintype "passive"))
      (node (ref "Q11") (pin "2") (pinfunction "E_2") (pintype "passive"))
      (node (ref "Q12") (pin "2") (pinfunction "E_2") (pintype "passive"))
      (node (ref "Q13") (pin "2") (pinfunction "E_2") (pintype "passive"))
      (node (ref "Q14") (pin "2") (pinfunction "E_2") (pintype "passive"))
      (node (ref "Q5") (pin "2") (pinfunction "E_2") (pintype "passive"))
      (node (ref "Q6") (pin "2") (pinfunction "E_2") (pintype "passive"))
      (node (ref "Q8") (pin "2") (pinfunction "E_2") (pintype "passive"))
      (node (ref "R15") (pin "1") (pinfunction "1_1") (pintype "passive"))
      (node (ref "R16") (pin "1") (pinfunction "1_1") (pintype "passive"))
      (node (ref "R47") (pin "1") (pinfunction "1_1") (pintype "passive"))
      (node (ref "R48") (pin "1") (pinfunction "1_1") (pintype "passive"))
      (node (ref "R51") (pin "1") (pinfunction "1_1") (pintype "passive"))
      (node (ref "R56") (pin "2") (pinfunction "2_2") (pintype "passive"))
      (node (ref "R6") (pin "1") (pinfunction "1_1") (pintype "passive"))
      (node (ref "U10") (pin "7") (pinfunction "VSS_7") (pintype "power_in"))
      (node (ref "U12") (pin "8") (pinfunction "8_8") (pintype "passive"))
      (node (ref "U13") (pin "10") (pinfunction "4Z_10") (pintype "passive"))
      (node (ref "U13") (pin "12") (pinfunction "4E_12") (pintype "passive"))
      (node (ref "U13") (pin "7") (pinfunction "VSS_7") (pintype "passive"))
      (node (ref "U14") (pin "1") (pinfunction "GND_1") (pintype "passive"))
      (node (ref "U16") (pin "7") (pinfunction "GND_7") (pintype "power_in"))
      (node (ref "U3") (pin "3") (pinfunction "IN+_3") (pintype "passive"))
      (node (ref "U4") (pin "2") (pinfunction "2_2") (pintype "passive"))
      (node (ref "U5") (pin "2") (pinfunction "2_2") (pintype "passive"))
      (node (ref "U6") (pin "8") (pinfunction "VSS_8") (pintype "passive"))
      (node (ref "VR1") (pin "1") (pinfunction "CCW_1") (pintype "passive"))
    )
    (net (code "53") (name "Net-(C1-Pad2)") (class "Default")
      (node (ref "C1") (pin "2") (pinfunction "2_2") (pintype "passive"))
      (node (ref "D12") (pin "A") (pinfunction "A_A") (pintype "passive"))
      (node (ref "R16") (pin "2") (pinfunction "2_2") (pintype "passive"))
      (node (ref "R17") (pin "2") (pinfunction "2_2") (pintype "passive"))
    )
    (net (code "54") (name "Net-(C4-Pad2)") (class "Default")
      (node (ref "C4") (pin "2") (pinfunction "2_2") (pintype "passive"))
      (node (ref "R14") (pin "2") (pinfunction "2_2") (pintype "passive"))
      (node (ref "R8") (pin "2") (pinfunction "2_2") (pintype "passive"))
    )
    (net (code "55") (name "Net-(C5-Pad2)") (class "Default")
      (node (ref "C5") (pin "2") (pinfunction "2_2") (pintype "passive"))
      (node (ref "R11") (pin "1") (pinfunction "1_1") (pintype "passive"))
      (node (ref "R12") (pin "1") (pinfunction "1_1") (pintype "passive"))
    )
    (net (code "56") (name "Net-(C7-Pad1)") (class "Default")
      (node (ref "C7") (pin "1") (pinfunction "1_1") (pintype "passive"))
      (node (ref "D14") (pin "C") (pinfunction "C_C") (pintype "passive"))
      (node (ref "R18") (pin "1") (pinfunction "1_1") (pintype "passive"))
      (node (ref "R19") (pin "1") (pinfunction "1_1") (pintype "passive"))
    )
    (net (code "57") (name "Net-(C7-Pad2)") (class "Default")
      (node (ref "C7") (pin "2") (pinfunction "2_2") (pintype "passive"))
      (node (ref "R18") (pin "2") (pinfunction "2_2") (pintype "passive"))
      (node (ref "R20") (pin "2") (pinfunction "2_2") (pintype "passive"))
    )
    (net (code "58") (name "Net-(C8-Pad1)") (class "Default")
      (node (ref "C8") (pin "1") (pinfunction "1_1") (pintype "passive"))
      (node (ref "D13") (pin "C") (pinfunction "C_C") (pintype "passive"))
      (node (ref "R21") (pin "2") (pinfunction "2_2") (pintype "passive"))
      (node (ref "R24") (pin "2") (pinfunction "2_2") (pintype "passive"))
    )
    (net (code "59") (name "Net-(C8-Pad2)") (class "Default")
      (node (ref "C8") (pin "2") (pinfunction "2_2") (pintype "passive"))
      (node (ref "R21") (pin "1") (pinfunction "1_1") (pintype "passive"))
      (node (ref "R22") (pin "2") (pinfunction "2_2") (pintype "passive"))
    )
    (net (code "60") (name "Net-(D1-PadA)") (class "Default")
      (node (ref "D1") (pin "A") (pinfunction "A_A") (pintype "passive"))
      (node (ref "D4") (pin "C") (pinfunction "C_C") (pintype "passive"))
    )
    (net (code "61") (name "Net-(D1-PadC)") (class "Default")
      (node (ref "D1") (pin "C") (pinfunction "C_C") (pintype "passive"))
      (node (ref "R5") (pin "1") (pinfunction "1_1") (pintype "passive"))
    )
    (net (code "62") (name "Net-(D10-PadC)") (class "Default")
      (node (ref "D10") (pin "C") (pinfunction "C_C") (pintype "passive"))
      (node (ref "R13") (pin "2") (pinfunction "2_2") (pintype "passive"))
    )
    (net (code "63") (name "Net-(D11-PadA)") (class "Default")
      (node (ref "D11") (pin "A") (pinfunction "A_A") (pintype "passive"))
      (node (ref "D12") (pin "C") (pinfunction "C_C") (pintype "passive"))
    )
    (net (code "64") (name "Net-(D15-PadA)") (class "Default")
      (node (ref "D15") (pin "A") (pinfunction "A_A") (pintype "passive"))
      (node (ref "R17") (pin "1") (pinfunction "1_1") (pintype "passive"))
    )
    (net (code "65") (name "Net-(D15-PadC)") (class "Default")
      (node (ref "D15") (pin "C") (pinfunction "C_C") (pintype "passive"))
      (node (ref "D16") (pin "A") (pinfunction "A_A") (pintype "passive"))
      (node (ref "D17") (pin "A") (pinfunction "A_A") (pintype "passive"))
      (node (ref "R23") (pin "2") (pinfunction "2_2") (pintype "passive"))
    )
    (net (code "66") (name "Net-(D20-PadC)") (class "Default")
      (node (ref "D20") (pin "C") (pinfunction "C_C") (pintype "passive"))
      (node (ref "D23") (pin "C") (pinfunction "C_C") (pintype "passive"))
      (node (ref "D24") (pin "C") (pinfunction "C_C") (pintype "passive"))
    )
    (net (code "67") (name "Net-(D21-PadA)") (class "Default")
      (node (ref "D21") (pin "A") (pinfunction "A_A") (pintype "passive"))
      (node (ref "D22") (pin "A") (pinfunction "A_A") (pintype "passive"))
      (node (ref "D23") (pin "A") (pinfunction "A_A") (pintype "passive"))
    )
    (net (code "68") (name "Net-(D25-PadC)") (class "Default")
      (node (ref "D25") (pin "C") (pinfunction "C_C") (pintype "passive"))
      (node (ref "R42") (pin "2") (pinfunction "2_2") (pintype "passive"))
    )
    (net (code "69") (name "Net-(D26-PadC)") (class "Default")
      (node (ref "D26") (pin "C") (pinfunction "C_C") (pintype "passive"))
      (node (ref "R43") (pin "1") (pinfunction "1_1") (pintype "passive"))
    )
    (net (code "70") (name "Net-(Q1-B)") (class "Default")
      (node (ref "Q1") (pin "1") (pinfunction "B_1") (pintype "passive"))
      (node (ref "R12") (pin "2") (pinfunction "2_2") (pintype "passive"))
    )
    (net (code "71") (name "Net-(Q1-C)") (class "Default")
      (node (ref "Q1") (pin "3") (pinfunction "C_3") (pintype "passive"))
      (node (ref "Q2") (pin "1") (pinfunction "B_1") (pintype "passive"))
      (node (ref "R1") (pin "2") (pinfunction "2_2") (pintype "passive"))
    )
    (net (code "72") (name "Net-(Q2-E)") (class "Default")
      (node (ref "D6") (pin "A") (pinfunction "A_A") (pintype "passive"))
      (node (ref "Q2") (pin "2") (pinfunction "E_2") (pintype "passive"))
    )
    (net (code "73") (name "Net-(Q3-B)") (class "Default")
      (node (ref "Q3") (pin "1") (pinfunction "B_1") (pintype "passive"))
      (node (ref "Q5") (pin "3") (pinfunction "C_3") (pintype "passive"))
      (node (ref "R2") (pin "1") (pinfunction "1_1") (pintype "passive"))
    )
    (net (code "74") (name "Net-(Q3-E)") (class "Default")
      (node (ref "D7") (pin "A") (pinfunction "A_A") (pintype "passive"))
      (node (ref "D8") (pin "A") (pinfunction "A_A") (pintype "passive"))
      (node (ref "Q3") (pin "2") (pinfunction "E_2") (pintype "passive"))
    )
    (net (code "75") (name "Net-(Q4-B)") (class "Default")
      (node (ref "C17") (pin "1") (pinfunction "1_1") (pintype "passive"))
      (node (ref "D2") (pin "C") (pinfunction "C_C") (pintype "passive"))
      (node (ref "D31") (pin "C") (pinfunction "C_C") (pintype "passive"))
      (node (ref "Q4") (pin "1") (pinfunction "B_1") (pintype "passive"))
      (node (ref "R56") (pin "1") (pinfunction "1_1") (pintype "passive"))
    )
    (net (code "76") (name "Net-(Q4-E)") (class "Default")
      (node (ref "Q4") (pin "2") (pinfunction "E_2") (pintype "passive"))
      (node (ref "R8") (pin "1") (pinfunction "1_1") (pintype "passive"))
    )
    (net (code "77") (name "Net-(Q5-B)") (class "Default")
      (node (ref "Q5") (pin "1") (pinfunction "B_1") (pintype "passive"))
      (node (ref "R14") (pin "1") (pinfunction "1_1") (pintype "passive"))
    )
    (net (code "78") (name "Net-(Q6-B)") (class "Default")
      (node (ref "C2") (pin "2") (pinfunction "2_2") (pintype "passive"))
      (node (ref "Q6") (pin "1") (pinfunction "B_1") (pintype "passive"))
      (node (ref "R7") (pin "2") (pinfunction "2_2") (pintype "passive"))
    )
    (net (code "79") (name "Net-(Q6-C)") (class "Default")
      (node (ref "D2") (pin "A") (pinfunction "A_A") (pintype "passive"))
      (node (ref "D5") (pin "C") (pinfunction "C_C") (pintype "passive"))
      (node (ref "Q6") (pin "3") (pinfunction "C_3") (pintype "passive"))
      (node (ref "R4") (pin "1") (pinfunction "1_1") (pintype "passive"))
    )
    (net (code "80") (name "Net-(Q7-B)") (class "Default")
      (node (ref "C3") (pin "1") (pinfunction "1_1") (pintype "passive"))
      (node (ref "D11") (pin "C") (pinfunction "C_C") (pintype "passive"))
      (node (ref "Q7") (pin "1") (pinfunction "B_1") (pintype "passive"))
      (node (ref "R6") (pin "2") (pinfunction "2_2") (pintype "passive"))
    )
    (net (code "81") (name "Net-(Q7-E)") (class "Default")
      (node (ref "Q7") (pin "2") (pinfunction "E_2") (pintype "passive"))
      (node (ref "R11") (pin "2") (pinfunction "2_2") (pintype "passive"))
    )
    (net (code "82") (name "Net-(Q9-B)") (class "Default")
      (node (ref "Q9") (pin "1") (pinfunction "B_1") (pintype "passive"))
      (node (ref "R19") (pin "2") (pinfunction "2_2") (pintype "passive"))
    )
    (net (code "83") (name "Net-(Q9-E)") (class "Default")
      (node (ref "Q9") (pin "3") (pinfunction "E_3") (pintype "passive"))
      (node (ref "VR1") (pin "2") (pinfunction "WIPER_2") (pintype "passive"))
    )
    (net (code "84") (name "Net-(Q10-B)") (class "Default")
      (node (ref "C6") (pin "2") (pinfunction "2_2") (pintype "passive"))
      (node (ref "Q10") (pin "1") (pinfunction "B_1") (pintype "passive"))
      (node (ref "R13") (pin "1") (pinfunction "1_1") (pintype "passive"))
      (node (ref "R15") (pin "2") (pinfunction "2_2") (pintype "passive"))
    )
    (net (code "85") (name "Net-(Q10-C)") (class "Default")
      (node (ref "Q10") (pin "3") (pinfunction "C_3") (pintype "passive"))
      (node (ref "U2") (pin "8") (pinfunction "8_8") (pintype "passive"))
    )
    (net (code "86") (name "Net-(Q11-B)") (class "Default")
      (node (ref "C13") (pin "2") (pinfunction "2_2") (pintype "passive"))
      (node (ref "Q11") (pin "1") (pinfunction "B_1") (pintype "passive"))
      (node (ref "R46") (pin "2") (pinfunction "2_2") (pintype "passive"))
      (node (ref "R47") (pin "2") (pinfunction "2_2") (pintype "passive"))
    )
    (net (code "87") (name "Net-(Q11-C)") (class "Default")
      (node (ref "Q11") (pin "3") (pinfunction "C_3") (pintype "passive"))
      (node (ref "Q8") (pin "1") (pinfunction "B_1") (pintype "passive"))
      (node (ref "R45") (pin "1") (pinfunction "1_1") (pintype "passive"))
    )
    (net (code "88") (name "Net-(Q12-B)") (class "Default")
      (node (ref "Q12") (pin "1") (pinfunction "B_1") (pintype "passive"))
      (node (ref "R48") (pin "2") (pinfunction "2_2") (pintype "passive"))
      (node (ref "R49") (pin "1") (pinfunction "1_1") (pintype "passive"))
    )
    (net (code "89") (name "Net-(Q12-C)") (class "Default")
      (node (ref "Q12") (pin "3") (pinfunction "C_3") (pintype "passive"))
      (node (ref "U15") (pin "1") (pinfunction "1_1") (pintype "passive"))
    )
    (net (code "90") (name "Net-(Q13-B)") (class "Default")
      (node (ref "C16") (pin "1") (pinfunction "1_1") (pintype "passive"))
      (node (ref "Q13") (pin "1") (pinfunction "B_1") (pintype "passive"))
      (node (ref "R51") (pin "2") (pinfunction "2_2") (pintype "passive"))
      (node (ref "R52") (pin "1") (pinfunction "1_1") (pintype "passive"))
    )
    (net (code "91") (name "Net-(Q13-C)") (class "Default")
      (node (ref "D31") (pin "A") (pinfunction "A_A") (pintype "passive"))
      (node (ref "Q13") (pin "3") (pinfunction "C_3") (pintype "passive"))
      (node (ref "R50") (pin "1") (pinfunction "1_1") (pintype "passive"))
    )
    (net (code "92") (name "Net-(Q14-B)") (class "Default")
      (node (ref "Q14") (pin "1") (pinfunction "B_1") (pintype "passive"))
      (node (ref "R54") (pin "1") (pinfunction "1_1") (pintype "passive"))
    )
    (net (code "93") (name "Net-(Q14-C)") (class "Default")
      (node (ref "Q14") (pin "3") (pinfunction "C_3") (pintype "passive"))
      (node (ref "R53") (pin "1") (pinfunction "1_1") (pintype "passive"))
    )
    (net (code "94") (name "Net-(R24-Pad1)") (class "Default")
      (node (ref "R24") (pin "1") (pinfunction "1_1") (pintype "passive"))
      (node (ref "R26") (pin "2") (pinfunction "2_2") (pintype "passive"))
    )
    (net (code "95") (name "Net-(R29-Pad2)") (class "Default")
      (node (ref "R29") (pin "2") (pinfunction "2_2") (pintype "passive"))
      (node (ref "U4") (pin "4") (pinfunction "4_4") (pintype "passive"))
    )
    (net (code "96") (name "Net-(R31-Pad1)") (class "Default")
      (node (ref "R31") (pin "1") (pinfunction "1_1") (pintype "passive"))
      (node (ref "U4") (pin "6") (pinfunction "6_6") (pintype "passive"))
    )
    (net (code "97") (name "Net-(R31-Pad2)") (class "Default")
      (node (ref "R31") (pin "2") (pinfunction "2_2") (pintype "passive"))
      (node (ref "U5") (pin "1") (pinfunction "1_1") (pintype "passive"))
    )
    (net (code "98") (name "Net-(R32-Pad1)") (class "Default")
      (node (ref "R32") (pin "1") (pinfunction "1_1") (pintype "passive"))
      (node (ref "R33") (pin "1") (pinfunction "1_1") (pintype "passive"))
      (node (ref "R34") (pin "1") (pinfunction "1_1") (pintype "passive"))
      (node (ref "R35") (pin "1") (pinfunction "1_1") (pintype "passive"))
      (node (ref "U12") (pin "4") (pinfunction "4_4") (pintype "passive"))
    )
    (net (code "99") (name "Net-(R32-Pad2)") (class "Default")
      (node (ref "R32") (pin "2") (pinfunction "2_2") (pintype "passive"))
      (node (ref "U5") (pin "3") (pinfunction "3_3") (pintype "passive"))
    )
    (net (code "100") (name "Net-(R33-Pad2)") (class "Default")
      (node (ref "R33") (pin "2") (pinfunction "2_2") (pintype "passive"))
      (node (ref "U7") (pin "4") (pinfunction "4_4") (pintype "passive"))
    )
    (net (code "101") (name "Net-(R34-Pad2)") (class "Default")
      (node (ref "R34") (pin "2") (pinfunction "2_2") (pintype "passive"))
      (node (ref "U8") (pin "3") (pinfunction "3_3") (pintype "passive"))
    )
    (net (code "102") (name "Net-(R35-Pad2)") (class "Default")
      (node (ref "R35") (pin "2") (pinfunction "2_2") (pintype "passive"))
      (node (ref "R36") (pin "2") (pinfunction "2_2") (pintype "passive"))
      (node (ref "U11") (pin "3") (pinfunction "3_3") (pintype "passive"))
      (node (ref "U12") (pin "2") (pinfunction "2_2") (pintype "passive"))
    )
    (net (code "103") (name "Net-(R36-Pad1)") (class "Default")
      (node (ref "R36") (pin "1") (pinfunction "1_1") (pintype "passive"))
      (node (ref "U9") (pin "3") (pinfunction "3_3") (pintype "passive"))
    )
    (net (code "104") (name "Net-(R37-Pad2)") (class "Default")
      (node (ref "R37") (pin "2") (pinfunction "2_2") (pintype "passive"))
      (node (ref "U7") (pin "2") (pinfunction "2_2") (pintype "passive"))
    )
    (net (code "105") (name "Net-(R38-Pad2)") (class "Default")
      (node (ref "R38") (pin "2") (pinfunction "2_2") (pintype "passive"))
      (node (ref "U8") (pin "2") (pinfunction "2_2") (pintype "passive"))
    )
    (net (code "106") (name "Net-(R39-Pad2)") (class "Default")
      (node (ref "R39") (pin "2") (pinfunction "2_2") (pintype "passive"))
      (node (ref "U9") (pin "2") (pinfunction "2_2") (pintype "passive"))
    )
    (net (code "107") (name "Net-(R53-Pad2)") (class "Default")
      (node (ref "R53") (pin "2") (pinfunction "2_2") (pintype "passive"))
      (node (ref "U11") (pin "1") (pinfunction "1_1") (pintype "passive"))
    )
    (net (code "108") (name "Net-(U1-B)") (class "Default")
      (node (ref "D4") (pin "A") (pinfunction "A_A") (pintype "passive"))
      (node (ref "D9") (pin "C") (pinfunction "C_C") (pintype "passive"))
      (node (ref "R10") (pin "2") (pinfunction "2_2") (pintype "passive"))
      (node (ref "U1") (pin "2") (pinfunction "B_2") (pintype "passive"))
    )
    (net (code "109") (name "Net-(U1-J)") (class "Default")
      (node (ref "C2") (pin "1") (pinfunction "1_1") (pintype "passive"))
      (node (ref "R7") (pin "1") (pinfunction "1_1") (pintype "passive"))
      (node (ref "U1") (pin "3") (pinfunction "J_3") (pintype "passive"))
    )
    (net (code "110") (name "Net-(U3-IN-)") (class "Default")
      (node (ref "C10") (pin "2") (pinfunction "2_2") (pintype "passive"))
      (node (ref "D18") (pin "C") (pinfunction "C_C") (pintype "passive"))
      (node (ref "D19") (pin "A") (pinfunction "A_A") (pintype "passive"))
      (node (ref "D22") (pin "C") (pinfunction "C_C") (pintype "passive"))
      (node (ref "D24") (pin "A") (pinfunction "A_A") (pintype "passive"))
      (node (ref "R26") (pin "1") (pinfunction "1_1") (pintype "passive"))
      (node (ref "R27") (pin "2") (pinfunction "2_2") (pintype "passive"))
      (node (ref "R28") (pin "2") (pinfunction "2_2") (pintype "passive"))
      (node (ref "R29") (pin "1") (pinfunction "1_1") (pintype "passive"))
      (node (ref "U3") (pin "2") (pinfunction "IN-_2") (pintype "passive"))
    )
    (net (code "111") (name "Net-(U3-OUT)") (class "Default")
      (node (ref "C10") (pin "1") (pinfunction "1_1") (pintype "passive"))
      (node (ref "D20") (pin "A") (pinfunction "A_A") (pintype "passive"))
      (node (ref "D21") (pin "C") (pinfunction "C_C") (pintype "passive"))
      (node (ref "R27") (pin "1") (pinfunction "1_1") (pintype "passive"))
      (node (ref "R30") (pin "2") (pinfunction "2_2") (pintype "passive"))
      (node (ref "U3") (pin "6") (pinfunction "OUT_6") (pintype "passive"))
    )
    (net (code "112") (name "Net-(U6-K)") (class "Default")
      (node (ref "D29") (pin "C") (pinfunction "C_C") (pintype "passive"))
      (node (ref "U6") (pin "12") (pinfunction "K_12") (pintype "passive"))
    )
    (net (code "113") (name "Net-(U6-L)") (class "Default")
      (node (ref "D30") (pin "C") (pinfunction "C_C") (pintype "passive"))
      (node (ref "U6") (pin "15") (pinfunction "L_15") (pintype "passive"))
    )
    (net (code "114") (name "Net-(U13-3Y)") (class "Default")
      (node (ref "R40") (pin "2") (pinfunction "2_2") (pintype "passive"))
      (node (ref "R42") (pin "1") (pinfunction "1_1") (pintype "passive"))
      (node (ref "U13") (pin "8") (pinfunction "3Y_8") (pintype "passive"))
    )
    (net (code "115") (name "Net-(U14-DISCH)") (class "Default")
      (node (ref "U14") (pin "7") (pinfunction "DISCH_7") (pintype "passive"))
      (node (ref "U15") (pin "6") (pinfunction "6_6") (pintype "passive"))
    )
    (net (code "116") (name "Net-(U14-THRES)") (class "Default")
      (node (ref "C12") (pin "2") (pinfunction "2_2") (pintype "passive"))
      (node (ref "R43") (pin "2") (pinfunction "2_2") (pintype "passive"))
      (node (ref "R44") (pin "2") (pinfunction "2_2") (pintype "passive"))
      (node (ref "U14") (pin "2") (pinfunction "TRIG_2") (pintype "passive"))
      (node (ref "U14") (pin "6") (pinfunction "THRES_6") (pintype "passive"))
    )
    (net (code "117") (name "VCC+12V0") (class "Default")
      (node (ref "C18") (pin "1") (pinfunction "1_1") (pintype "passive"))
      (node (ref "C19") (pin "2") (pinfunction "2_2") (pintype "passive"))
      (node (ref "C20") (pin "2") (pinfunction "2_2") (pintype "passive"))
      (node (ref "C21") (pin "1") (pinfunction "1_1") (pintype "passive"))
      (node (ref "C22") (pin "2") (pinfunction "2_2") (pintype "passive"))
      (node (ref "C23") (pin "1") (pinfunction "1_1") (pintype "passive"))
      (node (ref "Q2") (pin "3") (pinfunction "C_3") (pintype "passive"))
      (node (ref "Q3") (pin "3") (pinfunction "C_3") (pintype "passive"))
      (node (ref "Q4") (pin "3") (pinfunction "C_3") (pintype "passive"))
      (node (ref "Q7") (pin "3") (pinfunction "C_3") (pintype "passive"))
      (node (ref "R1") (pin "1") (pinfunction "1_1") (pintype "passive"))
      (node (ref "R2") (pin "2") (pinfunction "2_2") (pintype "passive"))
      (node (ref "R4") (pin "2") (pinfunction "2_2") (pintype "passive"))
      (node (ref "R45") (pin "2") (pinfunction "2_2") (pintype "passive"))
      (node (ref "R50") (pin "2") (pinfunction "2_2") (pintype "passive"))
      (node (ref "R57") (pin "1") (pinfunction "1_1") (pintype "passive"))
      (node (ref "R58") (pin "2") (pinfunction "2_2") (pintype "passive"))
      (node (ref "U1") (pin "1") (pinfunction "A_1") (pintype "passive"))
      (node (ref "U1") (pin "12") (pinfunction "G_12") (pintype "passive"))
      (node (ref "U1") (pin "13") (pinfunction "H_13") (pintype "passive"))
      (node (ref "U1") (pin "14") (pinfunction "VDD_14") (pintype "power_in"))
      (node (ref "U1") (pin "8") (pinfunction "E_8") (pintype "passive"))
      (node (ref "U1") (pin "9") (pinfunction "F_9") (pintype "passive"))
      (node (ref "U10") (pin "14") (pinfunction "VDD_14") (pintype "power_in"))
      (node (ref "U11") (pin "2") (pinfunction "2_2") (pintype "passive"))
      (node (ref "U13") (pin "14") (pinfunction "VDD_14") (pintype "power_in"))
      (node (ref "U14") (pin "8") (pinfunction "VCC_8") (pintype "power_in"))
      (node (ref "U15") (pin "2") (pinfunction "2_2") (pintype "passive"))
      (node (ref "U16") (pin "14") (pinfunction "VCC_14") (pintype "power_in"))
      (node (ref "U6") (pin "1") (pinfunction "VCC_1") (pintype "passive"))
      (node (ref "U7") (pin "1") (pinfunction "1_1") (pintype "passive"))
      (node (ref "U8") (pin "1") (pinfunction "1_1") (pintype "passive"))
      (node (ref "U9") (pin "1") (pinfunction "1_1") (pintype "passive"))
    )
    (net (code "118") (name "unconnected-(U1-K-Pad4)") (class "Default")
      (node (ref "U1") (pin "4") (pinfunction "K_4") (pintype "passive+no_connect"))
    )
    (net (code "119") (name "unconnected-(U1-L-Pad10)") (class "Default")
      (node (ref "U1") (pin "10") (pinfunction "L_10") (pintype "passive+no_connect"))
    )
    (net (code "120") (name "unconnected-(U1-M-Pad11)") (class "Default")
      (node (ref "U1") (pin "11") (pinfunction "M_11") (pintype "passive+no_connect"))
    )
    (net (code "121") (name "unconnected-(U2-Pad3)") (class "Default")
      (node (ref "U2") (pin "3") (pinfunction "3_3") (pintype "passive"))
    )
    (net (code "122") (name "unconnected-(U2-Pad6)") (class "Default")
      (node (ref "U2") (pin "6") (pinfunction "6_6") (pintype "passive"))
    )
    (net (code "123") (name "unconnected-(U3-NC-Pad5)") (class "Default")
      (node (ref "U3") (pin "5") (pinfunction "NC_5") (pintype "passive+no_connect"))
    )
    (net (code "124") (name "unconnected-(U3-VOS1-Pad1)") (class "Default")
      (node (ref "U3") (pin "1") (pinfunction "VOS1_1") (pintype "passive+no_connect"))
    )
    (net (code "125") (name "unconnected-(U3-VOS2-Pad8)") (class "Default")
      (node (ref "U3") (pin "8") (pinfunction "VOS2_8") (pintype "passive+no_connect"))
    )
    (net (code "126") (name "unconnected-(U6-NC-Pad13)") (class "Default")
      (node (ref "U6") (pin "13") (pinfunction "NC_13") (pintype "passive+no_connect"))
    )
    (net (code "127") (name "unconnected-(U6-NC-Pad16)") (class "Default")
      (node (ref "U6") (pin "16") (pinfunction "NC_16") (pintype "passive+no_connect"))
    )
    (net (code "128") (name "unconnected-(U10-D-Pad6)") (class "Default")
      (node (ref "U10") (pin "6") (pinfunction "D_6") (pintype "passive"))
    )
    (net (code "129") (name "unconnected-(U11-Pad5)") (class "Default")
      (node (ref "U11") (pin "5") (pinfunction "5_5") (pintype "passive+no_connect"))
    )
    (net (code "130") (name "unconnected-(U11-Pad6)") (class "Default")
      (node (ref "U11") (pin "6") (pinfunction "6_6") (pintype "passive+no_connect"))
    )
    (net (code "131") (name "unconnected-(U12-Pad3)") (class "Default")
      (node (ref "U12") (pin "3") (pinfunction "3_3") (pintype "passive+no_connect"))
    )
    (net (code "132") (name "unconnected-(U12-Pad6)") (class "Default")
      (node (ref "U12") (pin "6") (pinfunction "6_6") (pintype "passive+no_connect"))
    )
    (net (code "133") (name "unconnected-(U14-CONT-Pad5)") (class "Default")
      (node (ref "U14") (pin "5") (pinfunction "CONT_5") (pintype "passive+no_connect"))
    )
    (net (code "134") (name "unconnected-(U16A-CTRLVOLTAGE-Pad3)") (class "Default")
      (node (ref "U16") (pin "3") (pinfunction "CTRLVOLTAGE_3") (pintype "passive+no_connect"))
    )
    (net (code "135") (name "unconnected-(U16A-DISCHARGE-Pad1)") (class "Default")
      (node (ref "U16") (pin "1") (pinfunction "DISCHARGE_1") (pintype "passive+no_connect"))
    )
    (net (code "136") (name "unconnected-(U16B-CTRLVOLTAGE-Pad11)") (class "Default")
      (node (ref "U16") (pin "11") (pinfunction "CTRLVOLTAGE_11") (pintype "passive+no_connect"))
    )
    (net (code "137") (name "unconnected-(U16B-DISCHARGE-Pad13)") (class "Default")
      (node (ref "U16") (pin "13") (pinfunction "DISCHARGE_13") (pintype "passive+no_connect"))
    )
  )
)
